# main.net
KiCad netlist of a schematic drawn in EAGLE
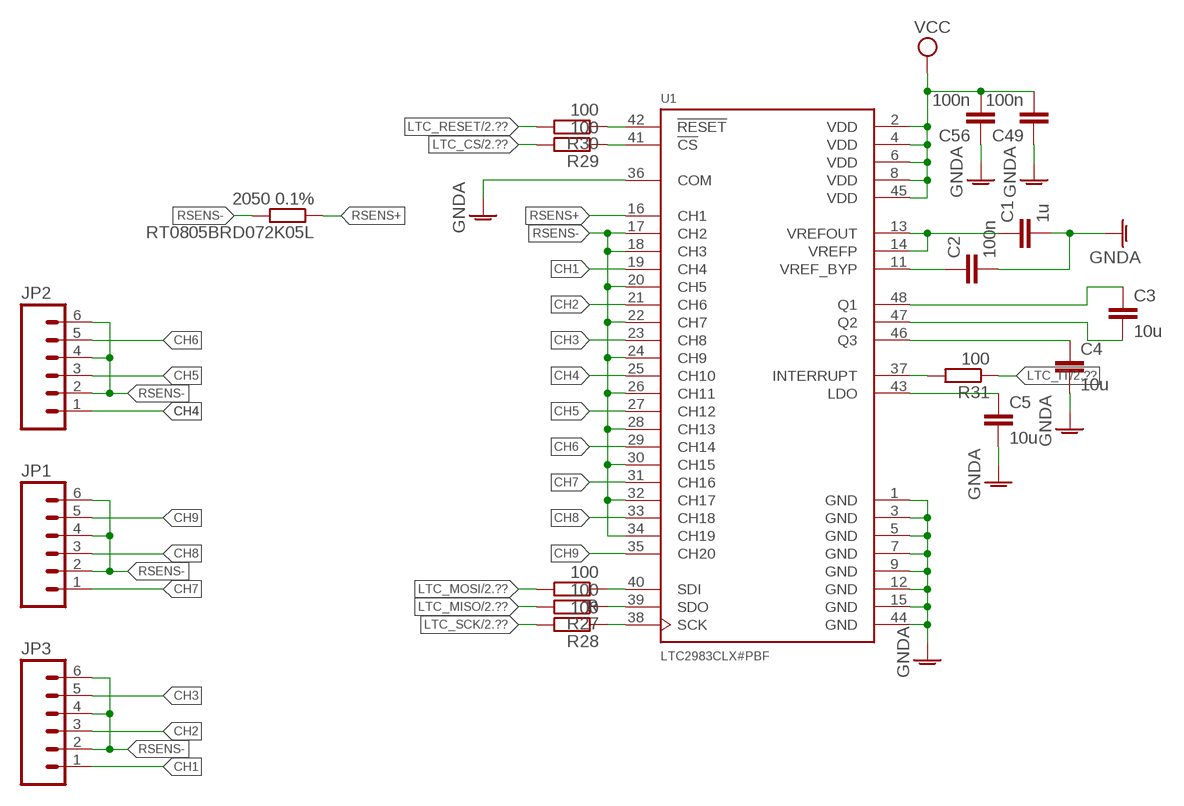
[diagram p0: schematic, sheet 1]
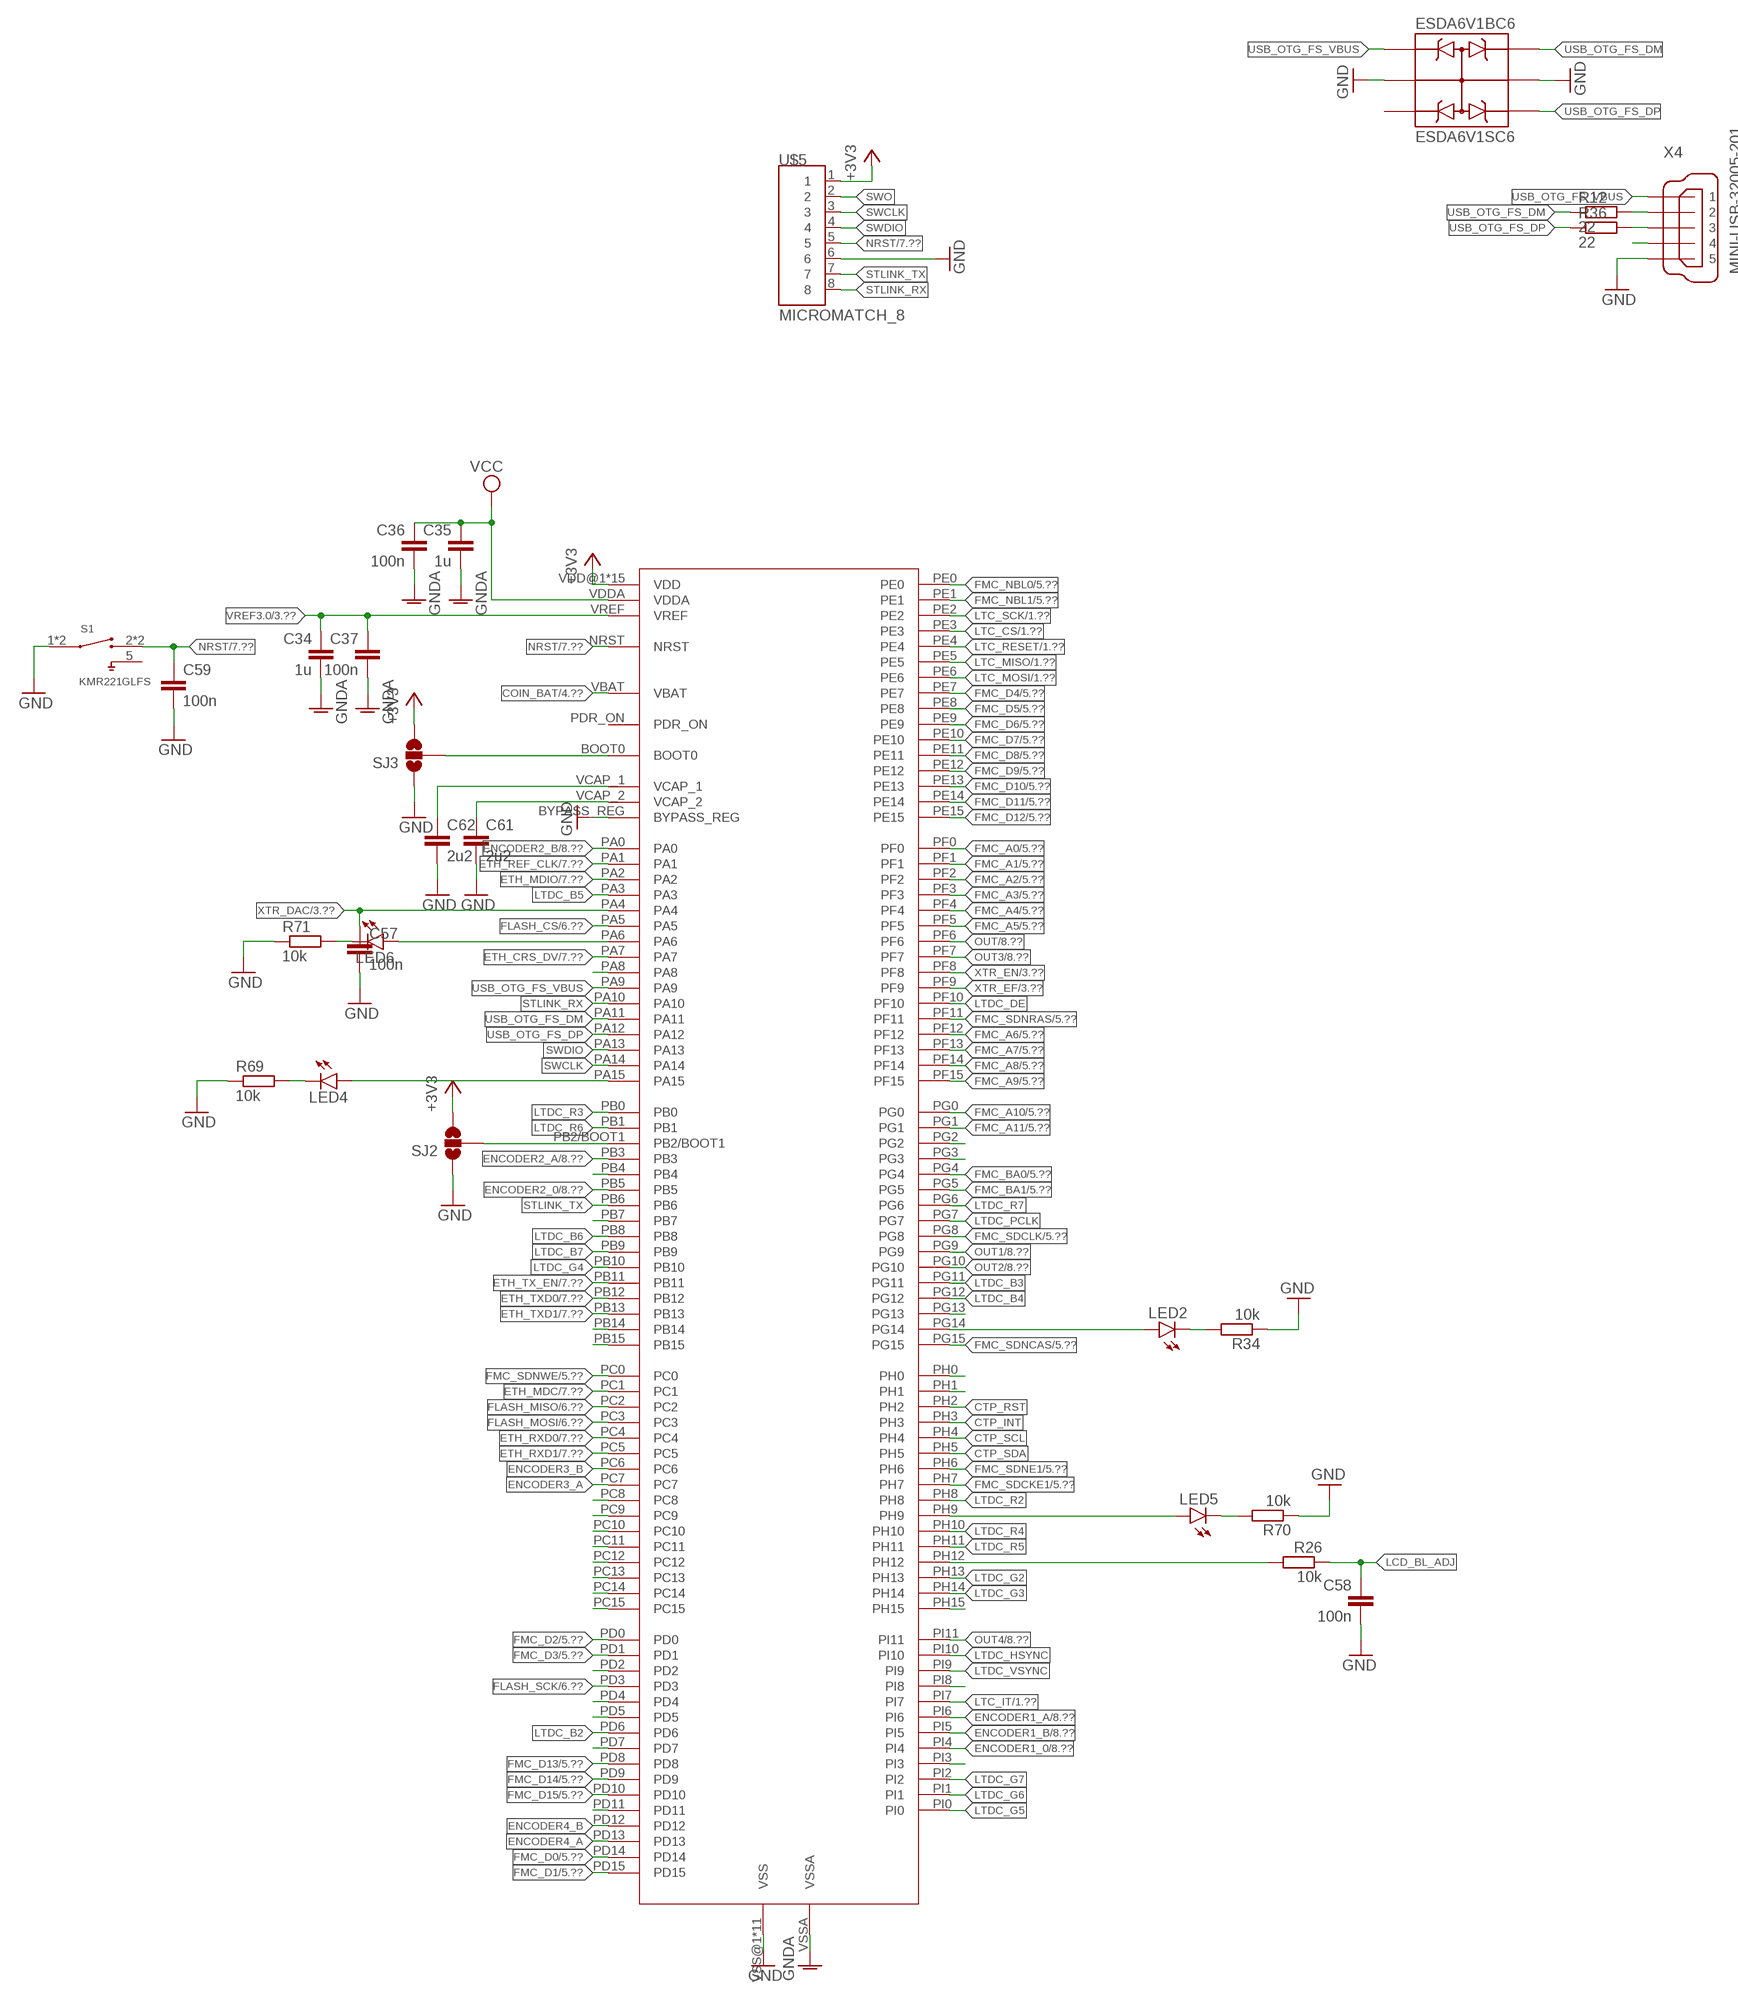
[diagram p1: schematic, sheet 2, part 1 of 2]
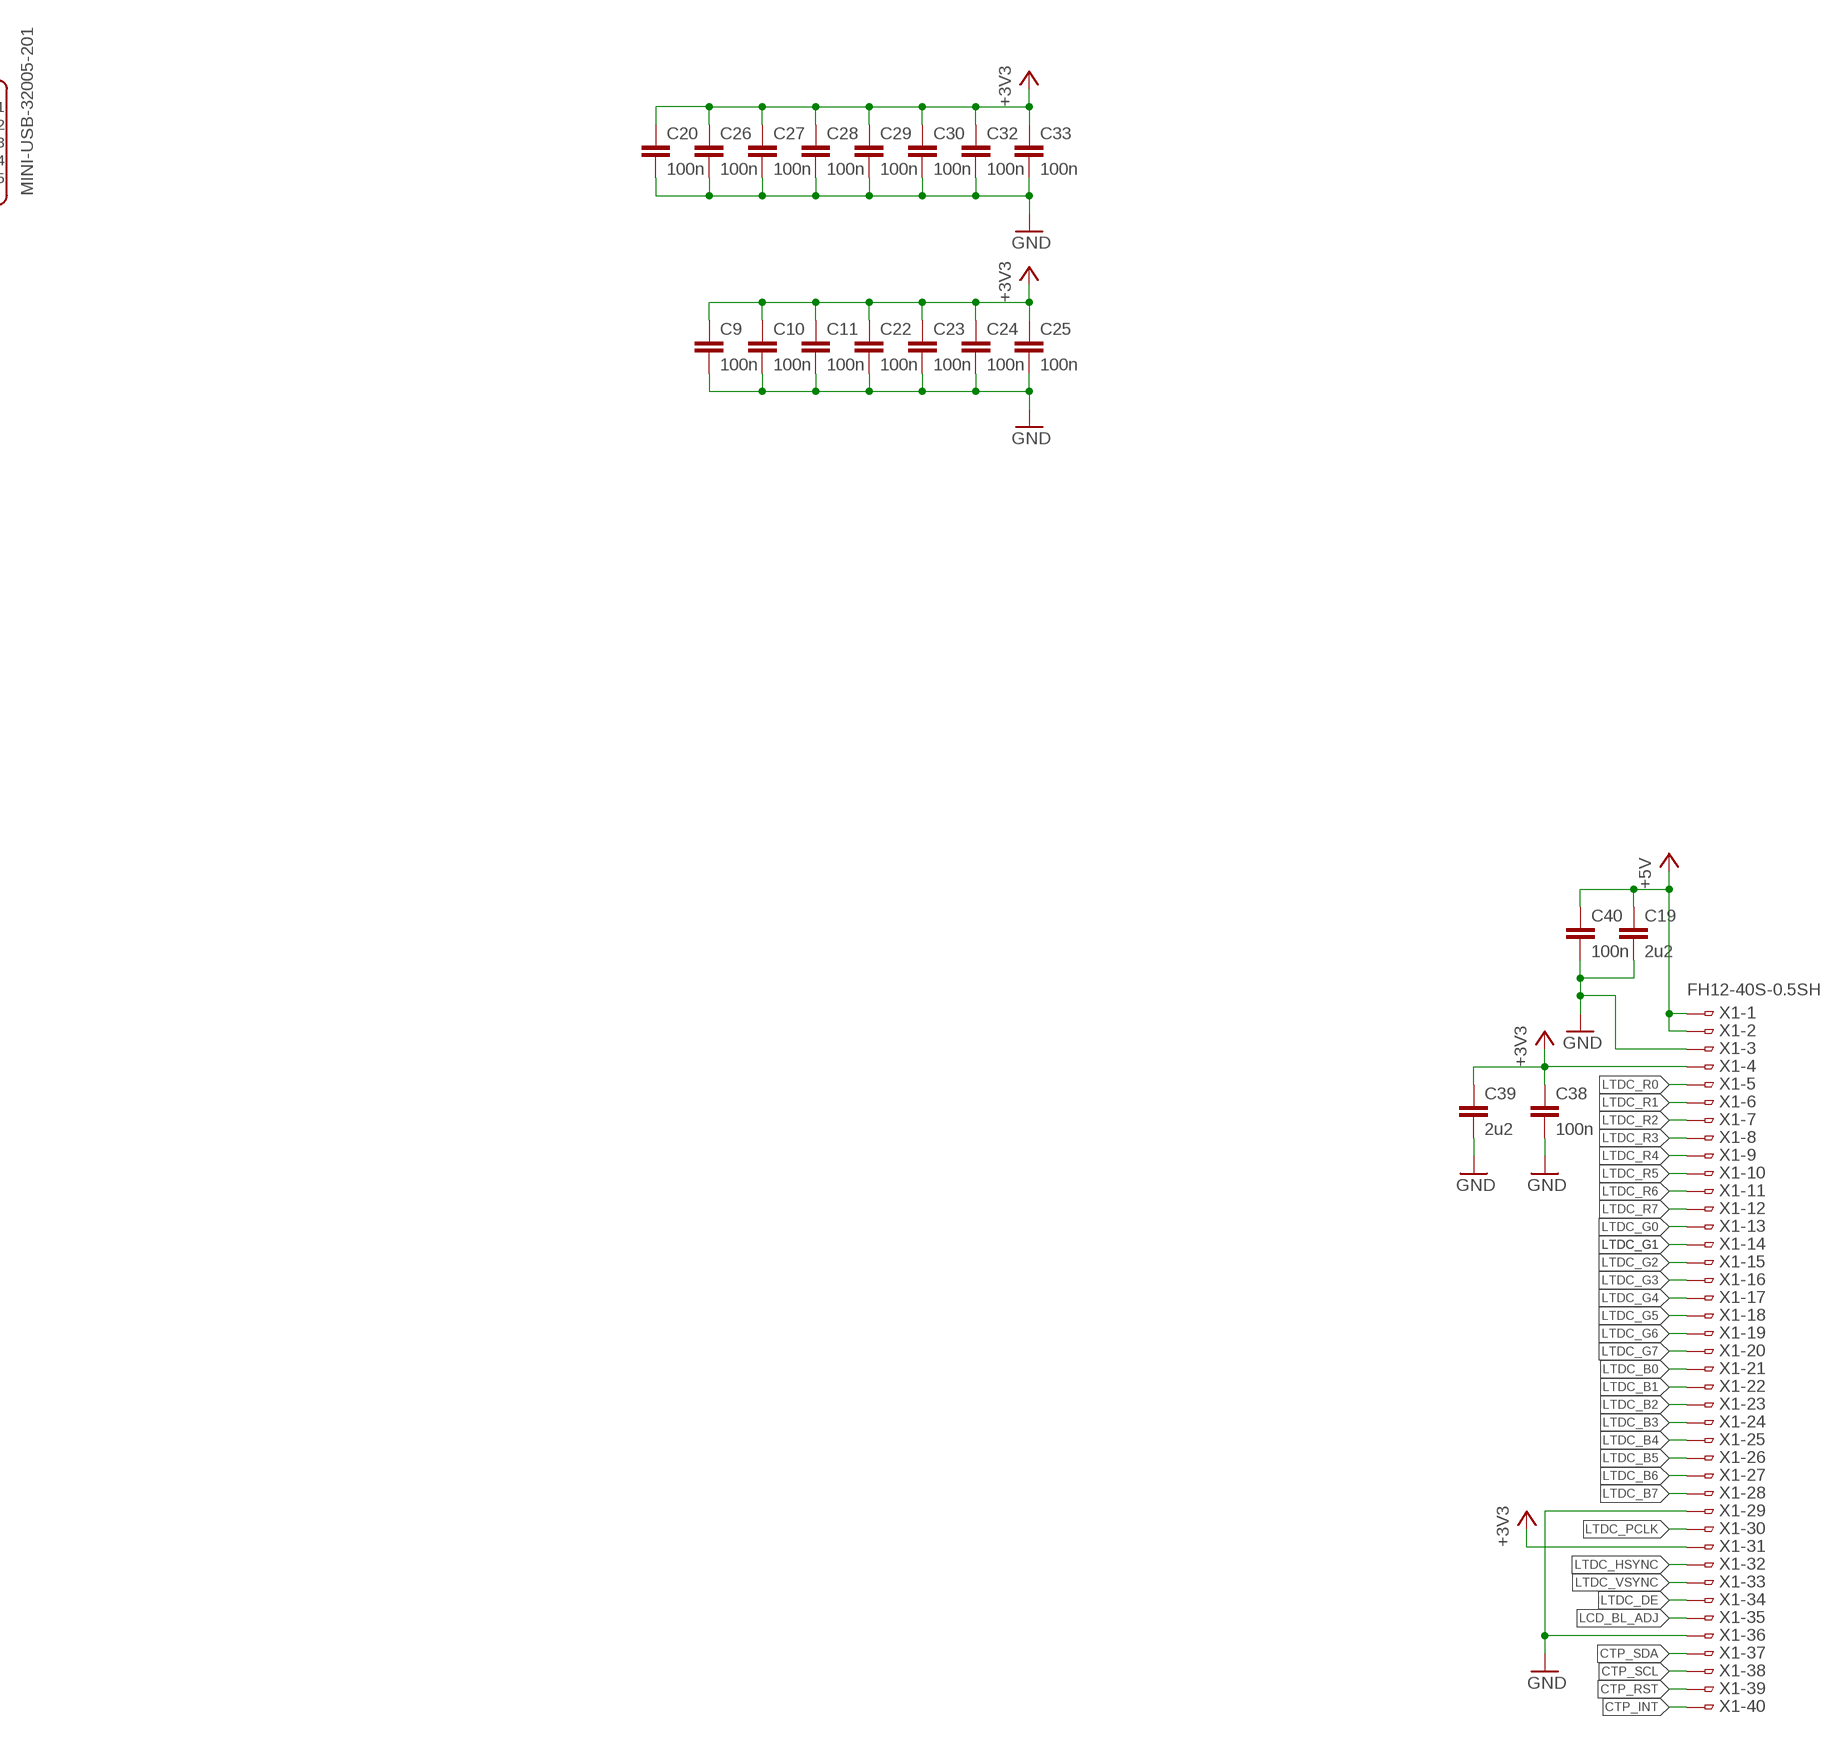
[diagram p2: schematic, sheet 2, part 2 of 2]
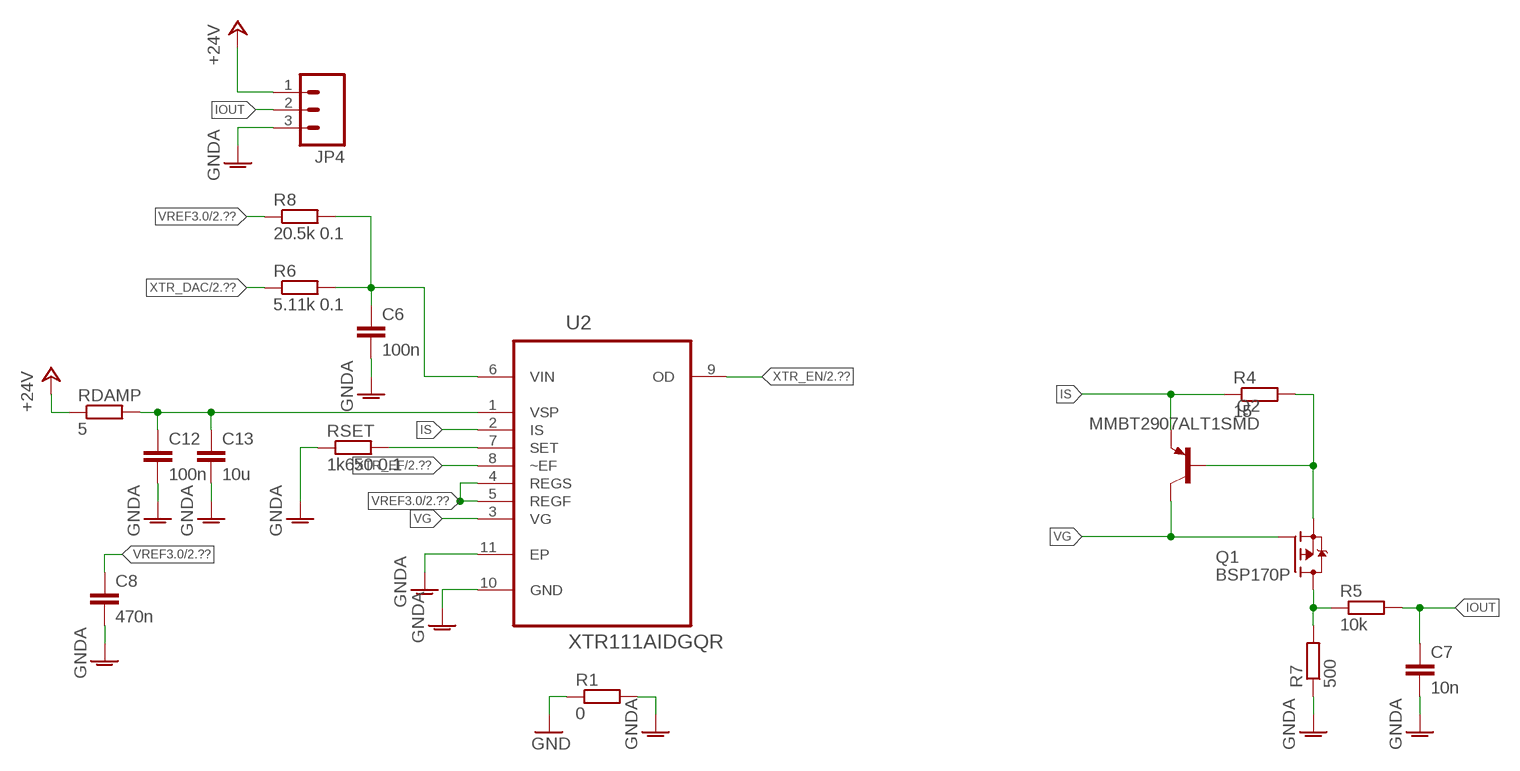
[diagram p3: schematic, sheet 3]
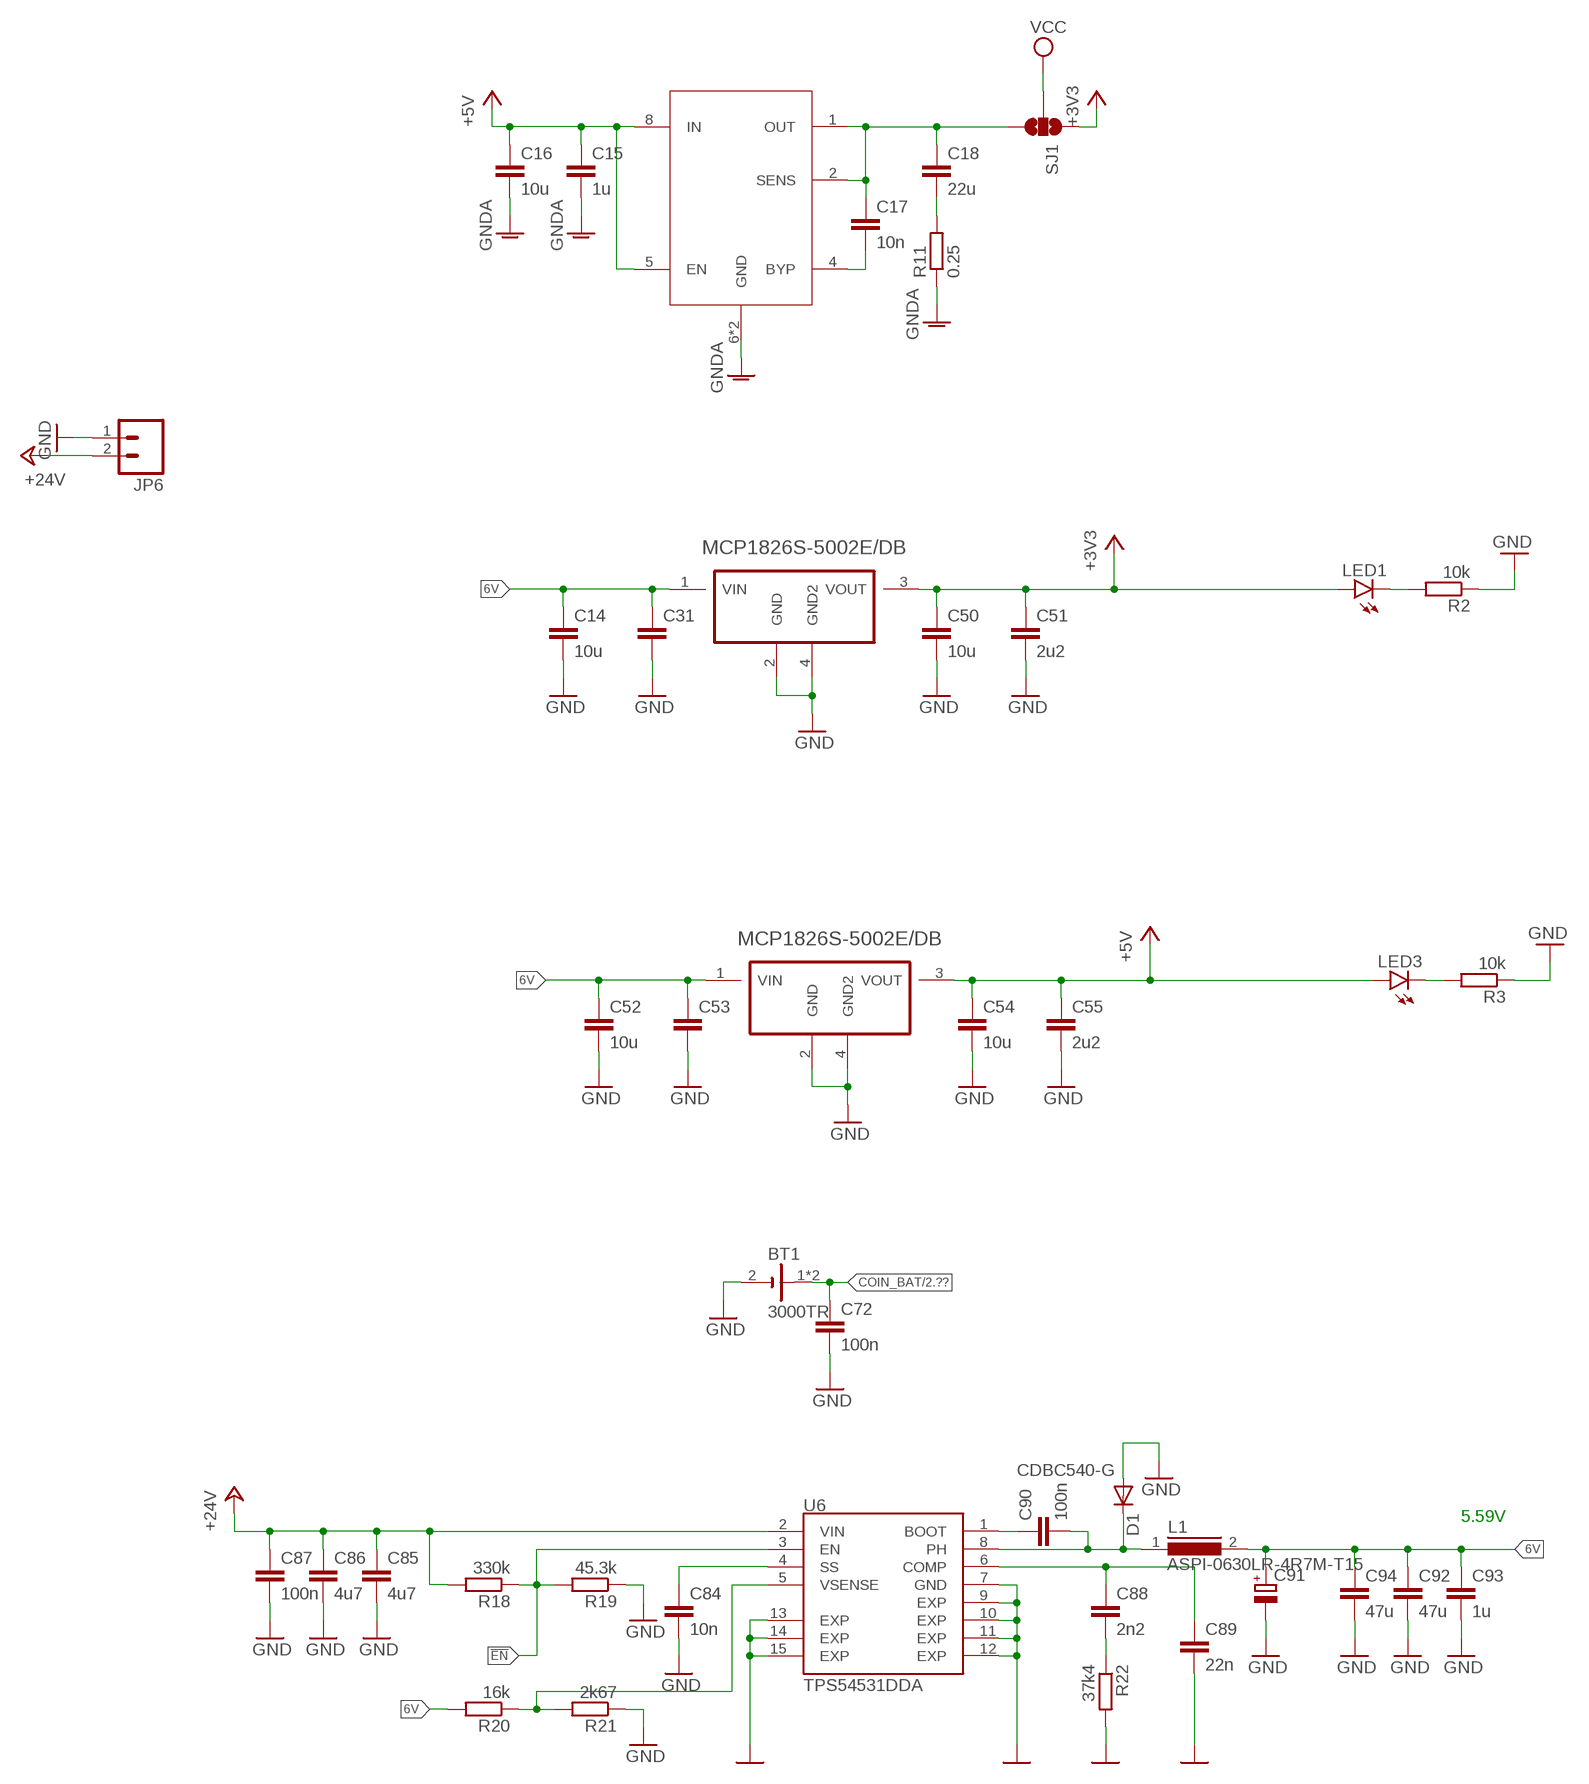
[diagram p4: schematic, sheet 4]
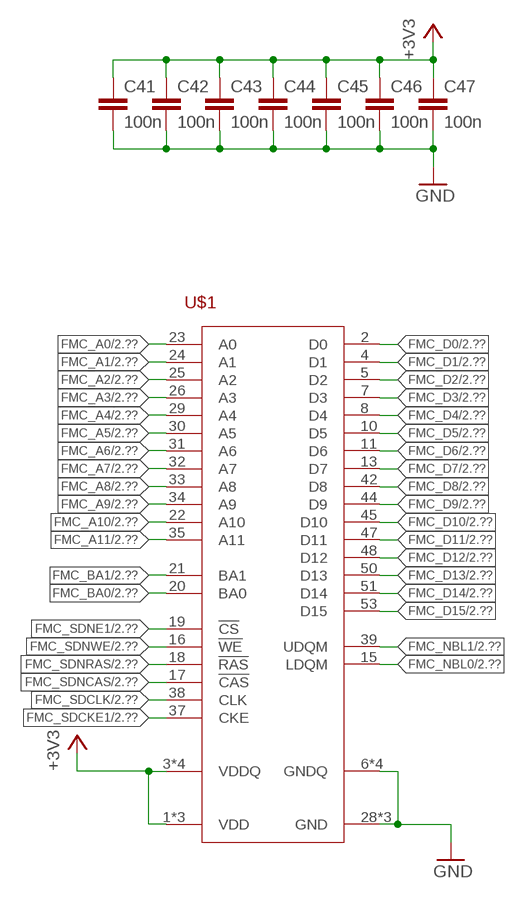
[diagram p5: schematic, sheet 5]
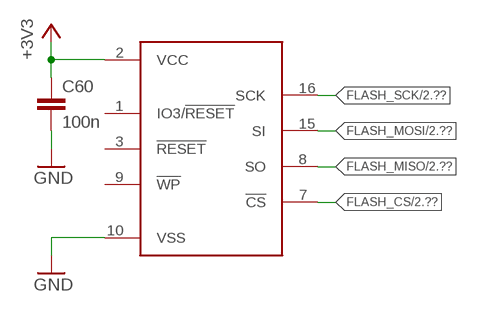
[diagram p6: schematic, sheet 6]
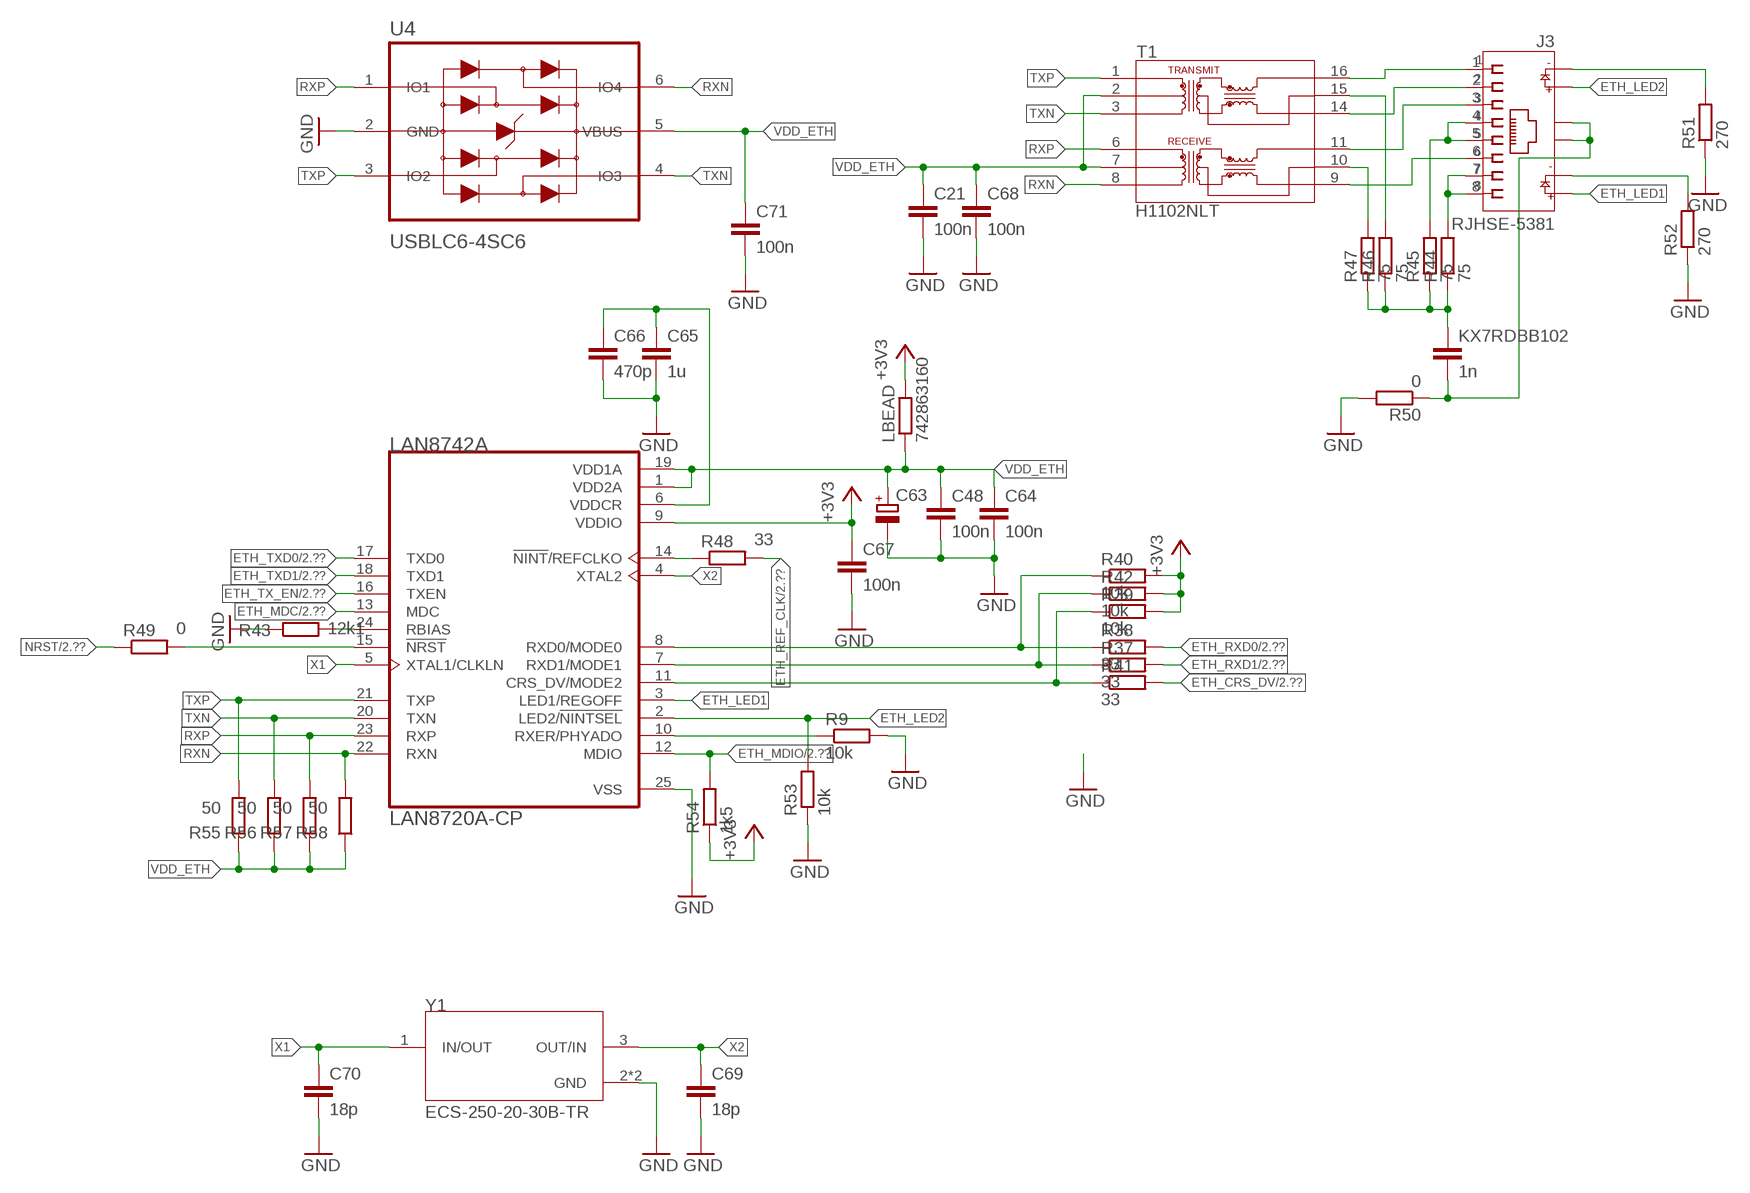
[diagram p7: schematic, sheet 7]
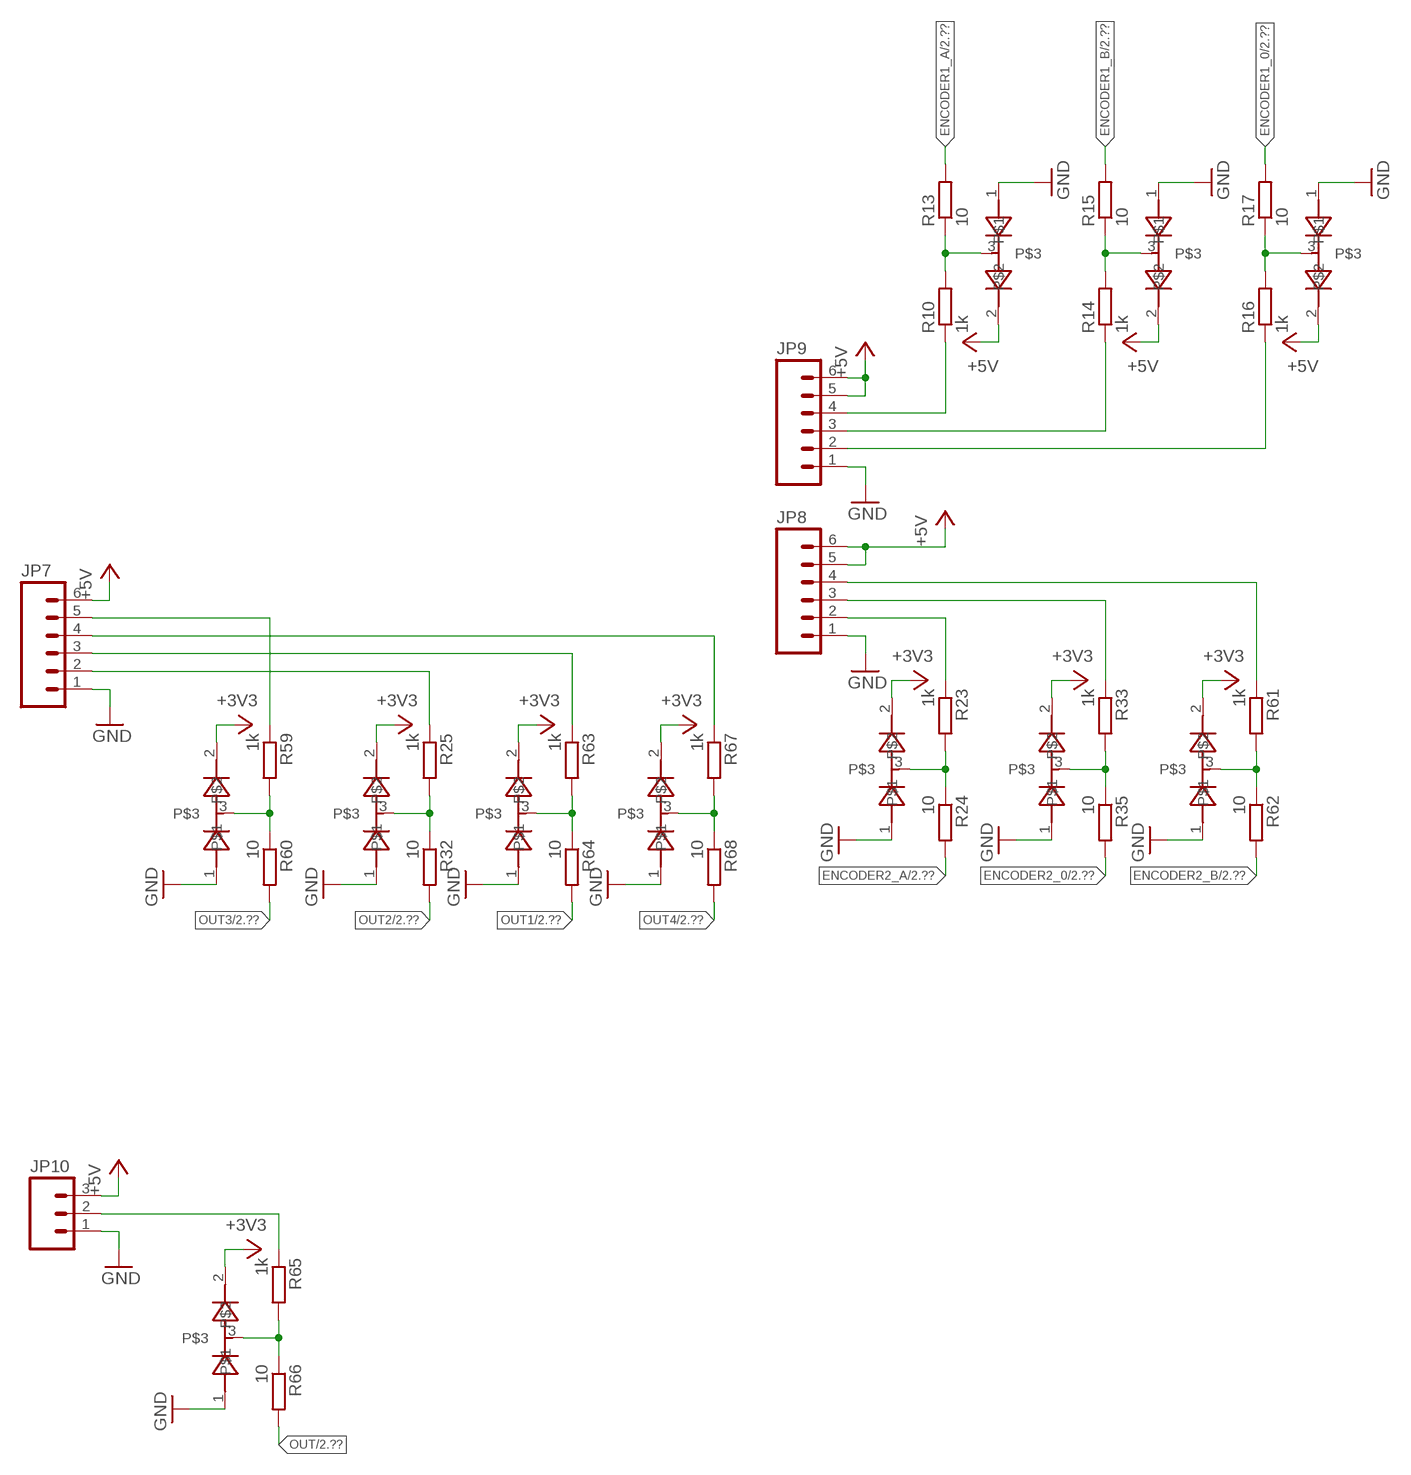
[diagram p8: schematic, sheet 8]

(export (version "E")
  (design (tool "Eeschema 10.0.6"))
  (components
    (comp (ref "C21")
      (value "100n")
      (footprint "eagle-import:C0603K")
      (libsource (lib "eagle-import") (part "rcl_334_C-EUC0603K"))
    )
    (comp (ref "C48")
      (value "100n")
      (footprint "eagle-import:C0603K")
      (libsource (lib "eagle-import") (part "rcl_334_C-EUC0603K"))
    )
    (comp (ref "C63")
      (value "CPOL-EUSMCA")
      (footprint "eagle-import:SMC_A")
      (libsource (lib "eagle-import") (part "CPOL-EUSMCA"))
    )
    (comp (ref "C64")
      (value "100n")
      (footprint "eagle-import:C0603K")
      (libsource (lib "eagle-import") (part "rcl_334_C-EUC0603K"))
    )
    (comp (ref "C65")
      (value "1u")
      (footprint "eagle-import:C0603K")
      (libsource (lib "eagle-import") (part "rcl_334_C-EUC0603K"))
    )
    (comp (ref "C66")
      (value "470p")
      (footprint "eagle-import:C0603K")
      (libsource (lib "eagle-import") (part "rcl_334_C-EUC0603K"))
    )
    (comp (ref "C67")
      (value "100n")
      (footprint "eagle-import:C0603K")
      (libsource (lib "eagle-import") (part "rcl_334_C-EUC0603K"))
    )
    (comp (ref "C68")
      (value "100n")
      (footprint "eagle-import:C0603K")
      (libsource (lib "eagle-import") (part "rcl_334_C-EUC0603K"))
    )
    (comp (ref "C69")
      (value "18p")
      (footprint "eagle-import:C0603K")
      (libsource (lib "eagle-import") (part "rcl_334_C-EUC0603K"))
    )
    (comp (ref "C70")
      (value "18p")
      (footprint "eagle-import:C0603K")
      (libsource (lib "eagle-import") (part "rcl_334_C-EUC0603K"))
    )
    (comp (ref "C71")
      (value "100n")
      (footprint "eagle-import:C0603K")
      (libsource (lib "eagle-import") (part "rcl_334_C-EUC0603K"))
    )
    (comp (ref "J3")
      (value "RJHSE-5381")
      (footprint "eagle-import:AMPHENOL_RJHSE-5381")
      (fields (field (name "MF") "Amphenol ICC"))
      (libsource (lib "eagle-import") (part "RJHSE-5381"))
    )
    (comp (ref "KX7RDBB102")
      (value "1n")
      (footprint "eagle-import:C1206K")
      (libsource (lib "eagle-import") (part "rcl_334_C-EUC1206K"))
    )
    (comp (ref "LAN8742A")
      (value "LAN8720A-CP")
      (footprint "eagle-import:QFN50P400X400X100-25N")
      (fields (field (name "MF") "SMSC"))
      (libsource (lib "eagle-import") (part "LAN8720A-CP"))
    )
    (comp (ref "LBEAD")
      (value "742863160")
      (footprint "eagle-import:R0603")
      (libsource (lib "eagle-import") (part "R-EU_R0603"))
    )
    (comp (ref "R9")
      (value "10k")
      (footprint "eagle-import:R0603")
      (libsource (lib "eagle-import") (part "R-EU_R0603"))
    )
    (comp (ref "R37")
      (value "33")
      (footprint "eagle-import:R0603")
      (libsource (lib "eagle-import") (part "R-EU_R0603"))
    )
    (comp (ref "R38")
      (value "33")
      (footprint "eagle-import:R0603")
      (libsource (lib "eagle-import") (part "R-EU_R0603"))
    )
    (comp (ref "R39")
      (value "10k")
      (footprint "eagle-import:R0603")
      (libsource (lib "eagle-import") (part "R-EU_R0603"))
    )
    (comp (ref "R40")
      (value "10k")
      (footprint "eagle-import:R0603")
      (libsource (lib "eagle-import") (part "R-EU_R0603"))
    )
    (comp (ref "R41")
      (value "33")
      (footprint "eagle-import:R0603")
      (libsource (lib "eagle-import") (part "R-EU_R0603"))
    )
    (comp (ref "R42")
      (value "10k")
      (footprint "eagle-import:R0603")
      (libsource (lib "eagle-import") (part "R-EU_R0603"))
    )
    (comp (ref "R43")
      (value "12k1")
      (footprint "eagle-import:R0603")
      (libsource (lib "eagle-import") (part "R-EU_R0603"))
    )
    (comp (ref "R44")
      (value "75")
      (footprint "eagle-import:R0603")
      (libsource (lib "eagle-import") (part "R-EU_R0603"))
    )
    (comp (ref "R45")
      (value "75")
      (footprint "eagle-import:R0603")
      (libsource (lib "eagle-import") (part "R-EU_R0603"))
    )
    (comp (ref "R46")
      (value "75")
      (footprint "eagle-import:R0603")
      (libsource (lib "eagle-import") (part "R-EU_R0603"))
    )
    (comp (ref "R47")
      (value "75")
      (footprint "eagle-import:R0603")
      (libsource (lib "eagle-import") (part "R-EU_R0603"))
    )
    (comp (ref "R48")
      (value "33")
      (footprint "eagle-import:R0603")
      (libsource (lib "eagle-import") (part "R-EU_R0603"))
    )
    (comp (ref "R49")
      (value "0")
      (footprint "eagle-import:R0603")
      (libsource (lib "eagle-import") (part "R-EU_R0603"))
    )
    (comp (ref "R50")
      (value "0")
      (footprint "eagle-import:R0603")
      (libsource (lib "eagle-import") (part "R-EU_R0603"))
    )
    (comp (ref "R51")
      (value "270")
      (footprint "eagle-import:R0603")
      (libsource (lib "eagle-import") (part "R-EU_R0603"))
    )
    (comp (ref "R52")
      (value "270")
      (footprint "eagle-import:R0603")
      (libsource (lib "eagle-import") (part "R-EU_R0603"))
    )
    (comp (ref "R53")
      (value "10k")
      (footprint "eagle-import:R0603")
      (libsource (lib "eagle-import") (part "R-EU_R0603"))
    )
    (comp (ref "R54")
      (value "1k5")
      (footprint "eagle-import:R0603")
      (libsource (lib "eagle-import") (part "R-EU_R0603"))
    )
    (comp (ref "R55")
      (value "50")
      (footprint "eagle-import:R0603")
      (libsource (lib "eagle-import") (part "R-EU_R0603"))
    )
    (comp (ref "R56")
      (value "50")
      (footprint "eagle-import:R0603")
      (libsource (lib "eagle-import") (part "R-EU_R0603"))
    )
    (comp (ref "R57")
      (value "50")
      (footprint "eagle-import:R0603")
      (libsource (lib "eagle-import") (part "R-EU_R0603"))
    )
    (comp (ref "R58")
      (value "50")
      (footprint "eagle-import:R0603")
      (libsource (lib "eagle-import") (part "R-EU_R0603"))
    )
    (comp (ref "T1")
      (value "H1102NLT")
      (footprint "eagle-import:XFMR_H1102NLT")
      (fields (field (name "MF") "Pulse Electronics"))
      (libsource (lib "eagle-import") (part "H1102NLT"))
    )
    (comp (ref "U4")
      (value "USBLC6-4SC6")
      (footprint "eagle-import:SOT95P280X145-6N")
      (fields (field (name "MF") "STMicroelectronics"))
      (libsource (lib "eagle-import") (part "USBLC6-4SC6"))
    )
    (comp (ref "Y1")
      (value "ECS-250-20-30B-TR")
      (footprint "eagle-import:XTAL_ECS-250-20-30B-TR")
      (fields (field (name "MF") "ECS Inc."))
      (libsource (lib "eagle-import") (part "ECS-250-20-30B-TR"))
    )
    (comp (ref "C6")
      (value "100n")
      (footprint "eagle-import:C0603K")
      (libsource (lib "eagle-import") (part "rcl_334_C-EUC0603K"))
    )
    (comp (ref "C7")
      (value "10n")
      (footprint "eagle-import:C0603K")
      (libsource (lib "eagle-import") (part "rcl_334_C-EUC0603K"))
    )
    (comp (ref "C8")
      (value "470n")
      (footprint "eagle-import:C0603K")
      (libsource (lib "eagle-import") (part "rcl_334_C-EUC0603K"))
    )
    (comp (ref "C12")
      (value "100n")
      (footprint "eagle-import:C0603K")
      (libsource (lib "eagle-import") (part "rcl_334_C-EUC0603K"))
    )
    (comp (ref "C13")
      (value "10u")
      (footprint "eagle-import:C0805")
      (libsource (lib "eagle-import") (part "rcl_334_C-EUC0805"))
    )
    (comp (ref "JP4")
      (value "M03SCREW")
      (footprint "eagle-import:SCREWTERMINAL-3.5MM-3")
      (libsource (lib "eagle-import") (part "M03SCREW"))
    )
    (comp (ref "Q1")
      (value "BSP170P")
      (footprint "eagle-import:SOT223")
      (libsource (lib "eagle-import") (part "BSP170P"))
    )
    (comp (ref "Q2")
      (value "MMBT2907ALT1SMD")
      (footprint "eagle-import:SOT23-BEC")
      (libsource (lib "eagle-import") (part "MMBT2907SMDALT1"))
    )
    (comp (ref "R1")
      (value "0")
      (footprint "eagle-import:R0603")
      (libsource (lib "eagle-import") (part "R-EU_R0603"))
    )
    (comp (ref "R4")
      (value "15")
      (footprint "eagle-import:R0603")
      (libsource (lib "eagle-import") (part "R-EU_R0603"))
    )
    (comp (ref "R5")
      (value "10k")
      (footprint "eagle-import:R0603")
      (libsource (lib "eagle-import") (part "R-EU_R0603"))
    )
    (comp (ref "R6")
      (value "5.11k 0.1")
      (footprint "eagle-import:R0805")
      (libsource (lib "eagle-import") (part "R-EU_R0805"))
    )
    (comp (ref "R7")
      (value "500")
      (footprint "eagle-import:R0603")
      (libsource (lib "eagle-import") (part "R-EU_R0603"))
    )
    (comp (ref "R8")
      (value "20.5k 0.1")
      (footprint "eagle-import:R0805")
      (libsource (lib "eagle-import") (part "R-EU_R0805"))
    )
    (comp (ref "RDAMP")
      (value "5")
      (footprint "eagle-import:R0603")
      (libsource (lib "eagle-import") (part "R-EU_R0603"))
    )
    (comp (ref "RSET")
      (value "1k650 0.1")
      (footprint "eagle-import:R0805")
      (libsource (lib "eagle-import") (part "R-EU_R0805"))
    )
    (comp (ref "U2")
      (value "XTR111AIDGQR")
      (footprint "eagle-import:SOP50P490X120-15N")
      (fields (field (name "MF") "Texas Instruments"))
      (libsource (lib "eagle-import") (part "XTR111AIDGQR"))
    )
    (comp (ref "C41")
      (value "100n")
      (footprint "eagle-import:C0603K")
      (libsource (lib "eagle-import") (part "rcl_334_C-EUC0603K"))
    )
    (comp (ref "C42")
      (value "100n")
      (footprint "eagle-import:C0603K")
      (libsource (lib "eagle-import") (part "rcl_334_C-EUC0603K"))
    )
    (comp (ref "C43")
      (value "100n")
      (footprint "eagle-import:C0603K")
      (libsource (lib "eagle-import") (part "rcl_334_C-EUC0603K"))
    )
    (comp (ref "C44")
      (value "100n")
      (footprint "eagle-import:C0603K")
      (libsource (lib "eagle-import") (part "rcl_334_C-EUC0603K"))
    )
    (comp (ref "C45")
      (value "100n")
      (footprint "eagle-import:C0603K")
      (libsource (lib "eagle-import") (part "rcl_334_C-EUC0603K"))
    )
    (comp (ref "C46")
      (value "100n")
      (footprint "eagle-import:C0603K")
      (libsource (lib "eagle-import") (part "rcl_334_C-EUC0603K"))
    )
    (comp (ref "C47")
      (value "100n")
      (footprint "eagle-import:C0603K")
      (libsource (lib "eagle-import") (part "rcl_334_C-EUC0603K"))
    )
    (comp (ref "U$1")
      (value "IS45S16400J")
      (footprint "eagle-import:TSOP54")
      (libsource (lib "eagle-import") (part "IS45S16400J"))
    )
    (comp (ref "C1")
      (value "1u")
      (footprint "eagle-import:C0603K")
      (libsource (lib "eagle-import") (part "rcl_334_C-EUC0603K"))
    )
    (comp (ref "C2")
      (value "100n")
      (footprint "eagle-import:C0603K")
      (libsource (lib "eagle-import") (part "rcl_334_C-EUC0603K"))
    )
    (comp (ref "C3")
      (value "10u")
      (footprint "eagle-import:C0805K")
      (libsource (lib "eagle-import") (part "rcl_334_C-EUC0805K"))
    )
    (comp (ref "C4")
      (value "10u")
      (footprint "eagle-import:C0805K")
      (libsource (lib "eagle-import") (part "rcl_334_C-EUC0805K"))
    )
    (comp (ref "C5")
      (value "10u")
      (footprint "eagle-import:C0805K")
      (libsource (lib "eagle-import") (part "rcl_334_C-EUC0805K"))
    )
    (comp (ref "C49")
      (value "100n")
      (footprint "eagle-import:C0603K")
      (libsource (lib "eagle-import") (part "rcl_334_C-EUC0603K"))
    )
    (comp (ref "C56")
      (value "100n")
      (footprint "eagle-import:C0603K")
      (libsource (lib "eagle-import") (part "rcl_334_C-EUC0603K"))
    )
    (comp (ref "JP1")
      (value "M063.5MM-6")
      (footprint "eagle-import:SCREWTERMINAL-3.5MM-6")
      (libsource (lib "eagle-import") (part "M063.5MM-6"))
    )
    (comp (ref "JP2")
      (value "M063.5MM-6")
      (footprint "eagle-import:SCREWTERMINAL-3.5MM-6")
      (libsource (lib "eagle-import") (part "M063.5MM-6"))
    )
    (comp (ref "JP3")
      (value "M063.5MM-6")
      (footprint "eagle-import:SCREWTERMINAL-3.5MM-6")
      (libsource (lib "eagle-import") (part "M063.5MM-6"))
    )
    (comp (ref "R")
      (value "100")
      (footprint "eagle-import:R0603")
      (libsource (lib "eagle-import") (part "R-EU_R0603"))
    )
    (comp (ref "R27")
      (value "100")
      (footprint "eagle-import:R0603")
      (libsource (lib "eagle-import") (part "R-EU_R0603"))
    )
    (comp (ref "R28")
      (value "100")
      (footprint "eagle-import:R0603")
      (libsource (lib "eagle-import") (part "R-EU_R0603"))
    )
    (comp (ref "R29")
      (value "100")
      (footprint "eagle-import:R0603")
      (libsource (lib "eagle-import") (part "R-EU_R0603"))
    )
    (comp (ref "R30")
      (value "100")
      (footprint "eagle-import:R0603")
      (libsource (lib "eagle-import") (part "R-EU_R0603"))
    )
    (comp (ref "R31")
      (value "100")
      (footprint "eagle-import:R0603")
      (libsource (lib "eagle-import") (part "R-EU_R0603"))
    )
    (comp (ref "RT0805BRD072K05L")
      (value "2050 0.1%")
      (footprint "eagle-import:R0805")
      (libsource (lib "eagle-import") (part "R-EU_R0805"))
    )
    (comp (ref "U1")
      (value "LTC2983CLX#PBF")
      (footprint "eagle-import:QFP50P900X900X160-48N")
      (fields (field (name "MF") "Linear Technology/Analog"))
      (libsource (lib "eagle-import") (part "LTC2983CLX#PBF"))
    )
    (comp (ref "BT1")
      (value "3000TR")
      (footprint "eagle-import:BAT_3000TR")
      (fields (field (name "MF") "Keystone"))
      (libsource (lib "eagle-import") (part "3000TR"))
    )
    (comp (ref "C14")
      (value "10u")
      (footprint "eagle-import:C0805K")
      (libsource (lib "eagle-import") (part "rcl_334_C-EUC0805K"))
    )
    (comp (ref "C15")
      (value "1u")
      (footprint "eagle-import:C0805")
      (libsource (lib "eagle-import") (part "C-EUC0805"))
    )
    (comp (ref "C16")
      (value "10u")
      (footprint "eagle-import:C0805")
      (libsource (lib "eagle-import") (part "C-EUC0805"))
    )
    (comp (ref "C17")
      (value "10n")
      (footprint "eagle-import:C0603K")
      (libsource (lib "eagle-import") (part "C-EUC0603K"))
    )
    (comp (ref "C18")
      (value "22u")
      (footprint "eagle-import:C1206")
      (libsource (lib "eagle-import") (part "C-EUC1206"))
    )
    (comp (ref "C31")
      (value "C-EUC0805K")
      (footprint "eagle-import:C0805K")
      (libsource (lib "eagle-import") (part "rcl_334_C-EUC0805K"))
    )
    (comp (ref "C50")
      (value "10u")
      (footprint "eagle-import:C0805K")
      (libsource (lib "eagle-import") (part "rcl_334_C-EUC0805K"))
    )
    (comp (ref "C51")
      (value "2u2")
      (footprint "eagle-import:C0805K")
      (libsource (lib "eagle-import") (part "rcl_334_C-EUC0805K"))
    )
    (comp (ref "C52")
      (value "10u")
      (footprint "eagle-import:C0805K")
      (libsource (lib "eagle-import") (part "rcl_334_C-EUC0805K"))
    )
    (comp (ref "C53")
      (value "C-EUC0805K")
      (footprint "eagle-import:C0805K")
      (libsource (lib "eagle-import") (part "rcl_334_C-EUC0805K"))
    )
    (comp (ref "C54")
      (value "10u")
      (footprint "eagle-import:C0805K")
      (libsource (lib "eagle-import") (part "rcl_334_C-EUC0805K"))
    )
    (comp (ref "C55")
      (value "2u2")
      (footprint "eagle-import:C0805K")
      (libsource (lib "eagle-import") (part "rcl_334_C-EUC0805K"))
    )
    (comp (ref "C72")
      (value "100n")
      (footprint "eagle-import:C0603K")
      (libsource (lib "eagle-import") (part "rcl_334_C-EUC0603K"))
    )
    (comp (ref "C84")
      (value "10n")
      (footprint "eagle-import:C0603K")
      (libsource (lib "eagle-import") (part "rcl_334_C-EUC0603K"))
    )
    (comp (ref "C85")
      (value "4u7")
      (footprint "eagle-import:C0805K")
      (libsource (lib "eagle-import") (part "rcl_334_C-EUC0805K"))
    )
    (comp (ref "C86")
      (value "4u7")
      (footprint "eagle-import:C0805K")
      (libsource (lib "eagle-import") (part "rcl_334_C-EUC0805K"))
    )
    (comp (ref "C87")
      (value "100n")
      (footprint "eagle-import:C0603K")
      (libsource (lib "eagle-import") (part "rcl_334_C-EUC0603K"))
    )
    (comp (ref "C88")
      (value "2n2")
      (footprint "eagle-import:C0603K")
      (libsource (lib "eagle-import") (part "rcl_334_C-EUC0603K"))
    )
    (comp (ref "C89")
      (value "22n")
      (footprint "eagle-import:C0603K")
      (libsource (lib "eagle-import") (part "rcl_334_C-EUC0603K"))
    )
    (comp (ref "C90")
      (value "100n")
      (footprint "eagle-import:C0603K")
      (libsource (lib "eagle-import") (part "rcl_334_C-EUC0603K"))
    )
    (comp (ref "C91")
      (value "CPOL-EUE5-6")
      (footprint "eagle-import:E5-6")
      (libsource (lib "eagle-import") (part "CPOL-EUE5-6"))
    )
    (comp (ref "C92")
      (value "47u")
      (footprint "eagle-import:C1210")
      (libsource (lib "eagle-import") (part "rcl_334_C-EUC1210"))
    )
    (comp (ref "C93")
      (value "1u")
      (footprint "eagle-import:C0603K")
      (libsource (lib "eagle-import") (part "rcl_334_C-EUC0603K"))
    )
    (comp (ref "C94")
      (value "47u")
      (footprint "eagle-import:C1210")
      (libsource (lib "eagle-import") (part "rcl_334_C-EUC1210"))
    )
    (comp (ref "D1")
      (value "CDBC540-G")
      (footprint "eagle-import:SMB")
      (libsource (lib "eagle-import") (part "DIODE-SMB"))
    )
    (comp (ref "JP6")
      (value "M023.5MM-NO_SILK")
      (footprint "eagle-import:SCREWTERMINAL-3.5MM-2-NS")
      (libsource (lib "eagle-import") (part "M023.5MM-NO_SILK"))
    )
    (comp (ref "L1")
      (value "ASPI-0630LR-4R7M-T15")
      (footprint "eagle-import:DR74")
      (libsource (lib "eagle-import") (part "DR74"))
    )
    (comp (ref "LED1")
      (value "LEDCHIPLED_0603")
      (footprint "eagle-import:CHIPLED_0603")
      (libsource (lib "eagle-import") (part "LEDCHIPLED_0603"))
    )
    (comp (ref "LED3")
      (value "LEDCHIPLED_0603")
      (footprint "eagle-import:CHIPLED_0603")
      (libsource (lib "eagle-import") (part "LEDCHIPLED_0603"))
    )
    (comp (ref "R2")
      (value "10k")
      (footprint "eagle-import:R0603")
      (libsource (lib "eagle-import") (part "R-EU_R0603"))
    )
    (comp (ref "R3")
      (value "10k")
      (footprint "eagle-import:R0603")
      (libsource (lib "eagle-import") (part "R-EU_R0603"))
    )
    (comp (ref "R11")
      (value "0.25")
      (footprint "eagle-import:R0603")
      (libsource (lib "eagle-import") (part "R-EU_R0603"))
    )
    (comp (ref "R18")
      (value "330k")
      (footprint "eagle-import:R0603")
      (libsource (lib "eagle-import") (part "R-EU_R0603"))
    )
    (comp (ref "R19")
      (value "45.3k")
      (footprint "eagle-import:R0603")
      (libsource (lib "eagle-import") (part "R-EU_R0603"))
    )
    (comp (ref "R20")
      (value "16k")
      (footprint "eagle-import:R0603")
      (libsource (lib "eagle-import") (part "R-EU_R0603"))
    )
    (comp (ref "R21")
      (value "2k67")
      (footprint "eagle-import:R0603")
      (libsource (lib "eagle-import") (part "R-EU_R0603"))
    )
    (comp (ref "R22")
      (value "37k4")
      (footprint "eagle-import:R0603")
      (libsource (lib "eagle-import") (part "R-EU_R0603"))
    )
    (comp (ref "SJ1")
      (value "SOLDERJUMPER_2WAYS")
      (footprint "eagle-import:SJ_3")
      (libsource (lib "eagle-import") (part "SOLDERJUMPER_2WAYS"))
    )
    (comp (ref "U$2")
      (value "IFX5444")
      (footprint "eagle-import:SOIC8")
      (libsource (lib "eagle-import") (part "IFX5444"))
    )
    (comp (ref "U3")
      (value "MCP1826S-5002E/DB")
      (footprint "eagle-import:SOT230P700X180-4N")
      (fields (field (name "MF") "Microchip"))
      (libsource (lib "eagle-import") (part "MCP1826S-5002E/DB"))
    )
    (comp (ref "U5")
      (value "MCP1826S-5002E/DB")
      (footprint "eagle-import:SOT230P700X180-4N")
      (fields (field (name "MF") "Microchip"))
      (libsource (lib "eagle-import") (part "MCP1826S-5002E/DB"))
    )
    (comp (ref "U6")
      (value "TPS54531DDA")
      (footprint "eagle-import:SOIC127P600X170-9N")
      (fields (field (name "MF") "Texas Instruments"))
      (libsource (lib "eagle-import") (part "TPS54531DDA"))
    )
    (comp (ref "C9")
      (value "100n")
      (footprint "eagle-import:C0603K")
      (libsource (lib "eagle-import") (part "rcl_334_C-EUC0603K"))
    )
    (comp (ref "C10")
      (value "100n")
      (footprint "eagle-import:C0603K")
      (libsource (lib "eagle-import") (part "rcl_334_C-EUC0603K"))
    )
    (comp (ref "C11")
      (value "100n")
      (footprint "eagle-import:C0603K")
      (libsource (lib "eagle-import") (part "rcl_334_C-EUC0603K"))
    )
    (comp (ref "C19")
      (value "2u2")
      (footprint "eagle-import:C0805K")
      (libsource (lib "eagle-import") (part "rcl_334_C-EUC0805K"))
    )
    (comp (ref "C20")
      (value "100n")
      (footprint "eagle-import:C0603K")
      (libsource (lib "eagle-import") (part "rcl_334_C-EUC0603K"))
    )
    (comp (ref "C22")
      (value "100n")
      (footprint "eagle-import:C0603K")
      (libsource (lib "eagle-import") (part "rcl_334_C-EUC0603K"))
    )
    (comp (ref "C23")
      (value "100n")
      (footprint "eagle-import:C0603K")
      (libsource (lib "eagle-import") (part "rcl_334_C-EUC0603K"))
    )
    (comp (ref "C24")
      (value "100n")
      (footprint "eagle-import:C0603K")
      (libsource (lib "eagle-import") (part "rcl_334_C-EUC0603K"))
    )
    (comp (ref "C25")
      (value "100n")
      (footprint "eagle-import:C0603K")
      (libsource (lib "eagle-import") (part "rcl_334_C-EUC0603K"))
    )
    (comp (ref "C26")
      (value "100n")
      (footprint "eagle-import:C0603K")
      (libsource (lib "eagle-import") (part "rcl_334_C-EUC0603K"))
    )
    (comp (ref "C27")
      (value "100n")
      (footprint "eagle-import:C0603K")
      (libsource (lib "eagle-import") (part "rcl_334_C-EUC0603K"))
    )
    (comp (ref "C28")
      (value "100n")
      (footprint "eagle-import:C0603K")
      (libsource (lib "eagle-import") (part "rcl_334_C-EUC0603K"))
    )
    (comp (ref "C29")
      (value "100n")
      (footprint "eagle-import:C0603K")
      (libsource (lib "eagle-import") (part "rcl_334_C-EUC0603K"))
    )
    (comp (ref "C30")
      (value "100n")
      (footprint "eagle-import:C0603K")
      (libsource (lib "eagle-import") (part "rcl_334_C-EUC0603K"))
    )
    (comp (ref "C32")
      (value "100n")
      (footprint "eagle-import:C0603K")
      (libsource (lib "eagle-import") (part "rcl_334_C-EUC0603K"))
    )
    (comp (ref "C33")
      (value "100n")
      (footprint "eagle-import:C0603K")
      (libsource (lib "eagle-import") (part "rcl_334_C-EUC0603K"))
    )
    (comp (ref "C34")
      (value "1u")
      (footprint "eagle-import:C0805K")
      (libsource (lib "eagle-import") (part "rcl_334_C-EUC0805K"))
    )
    (comp (ref "C35")
      (value "1u")
      (footprint "eagle-import:C0805K")
      (libsource (lib "eagle-import") (part "rcl_334_C-EUC0805K"))
    )
    (comp (ref "C36")
      (value "100n")
      (footprint "eagle-import:C0603K")
      (libsource (lib "eagle-import") (part "rcl_334_C-EUC0603K"))
    )
    (comp (ref "C37")
      (value "100n")
      (footprint "eagle-import:C0603K")
      (libsource (lib "eagle-import") (part "rcl_334_C-EUC0603K"))
    )
    (comp (ref "C38")
      (value "100n")
      (footprint "eagle-import:C0805")
      (libsource (lib "eagle-import") (part "C-EUC0805"))
    )
    (comp (ref "C39")
      (value "2u2")
      (footprint "eagle-import:C0805K")
      (libsource (lib "eagle-import") (part "rcl_334_C-EUC0805K"))
    )
    (comp (ref "C40")
      (value "100n")
      (footprint "eagle-import:C0805")
      (libsource (lib "eagle-import") (part "C-EUC0805"))
    )
    (comp (ref "C57")
      (value "100n")
      (footprint "eagle-import:C0603K")
      (libsource (lib "eagle-import") (part "rcl_334_C-EUC0603K"))
    )
    (comp (ref "C58")
      (value "100n")
      (footprint "eagle-import:C0603K")
      (libsource (lib "eagle-import") (part "rcl_334_C-EUC0603K"))
    )
    (comp (ref "C59")
      (value "100n")
      (footprint "eagle-import:C0603K")
      (libsource (lib "eagle-import") (part "rcl_334_C-EUC0603K"))
    )
    (comp (ref "C61")
      (value "2u2")
      (footprint "eagle-import:C0805K")
      (libsource (lib "eagle-import") (part "rcl_334_C-EUC0805K"))
    )
    (comp (ref "C62")
      (value "2u2")
      (footprint "eagle-import:C0805K")
      (libsource (lib "eagle-import") (part "rcl_334_C-EUC0805K"))
    )
    (comp (ref "ESDA6V1BC6")
      (value "ESDA6V1SC6")
      (footprint "eagle-import:SOT95P280X145-6N")
      (fields (field (name "MF") "STMicroelectronics"))
      (libsource (lib "eagle-import") (part "ESDA6V1SC6"))
    )
    (comp (ref "LED2")
      (value "LEDCHIPLED_0603")
      (footprint "eagle-import:CHIPLED_0603")
      (libsource (lib "eagle-import") (part "LEDCHIPLED_0603"))
    )
    (comp (ref "LED4")
      (value "LEDCHIPLED_0603")
      (footprint "eagle-import:CHIPLED_0603")
      (libsource (lib "eagle-import") (part "LEDCHIPLED_0603"))
    )
    (comp (ref "LED5")
      (value "LEDCHIPLED_0603")
      (footprint "eagle-import:CHIPLED_0603")
      (libsource (lib "eagle-import") (part "LEDCHIPLED_0603"))
    )
    (comp (ref "LED6")
      (value "LEDCHIPLED_0603")
      (footprint "eagle-import:CHIPLED_0603")
      (libsource (lib "eagle-import") (part "LEDCHIPLED_0603"))
    )
    (comp (ref "R12")
      (value "22")
      (footprint "eagle-import:R0603")
      (libsource (lib "eagle-import") (part "R-EU_R0603"))
    )
    (comp (ref "R26")
      (value "10k")
      (footprint "eagle-import:R0603")
      (libsource (lib "eagle-import") (part "R-EU_R0603"))
    )
    (comp (ref "R34")
      (value "10k")
      (footprint "eagle-import:R0603")
      (libsource (lib "eagle-import") (part "R-EU_R0603"))
    )
    (comp (ref "R36")
      (value "22")
      (footprint "eagle-import:R0603")
      (libsource (lib "eagle-import") (part "R-EU_R0603"))
    )
    (comp (ref "R69")
      (value "10k")
      (footprint "eagle-import:R0603")
      (libsource (lib "eagle-import") (part "R-EU_R0603"))
    )
    (comp (ref "R70")
      (value "10k")
      (footprint "eagle-import:R0603")
      (libsource (lib "eagle-import") (part "R-EU_R0603"))
    )
    (comp (ref "R71")
      (value "10k")
      (footprint "eagle-import:R0603")
      (libsource (lib "eagle-import") (part "R-EU_R0603"))
    )
    (comp (ref "S1")
      (value "KMR221GLFS")
      (footprint "eagle-import:SW_KMR221GLFS")
      (fields (field (name "MF") "C&K Components"))
      (libsource (lib "eagle-import") (part "KMR221GLFS"))
    )
    (comp (ref "SJ2")
      (value "SOLDERJUMPER_2WAYS")
      (footprint "eagle-import:SJ_3")
      (libsource (lib "eagle-import") (part "SOLDERJUMPER_2WAYS"))
    )
    (comp (ref "SJ3")
      (value "SOLDERJUMPER_2WAYS")
      (footprint "eagle-import:SJ_3")
      (libsource (lib "eagle-import") (part "SOLDERJUMPER_2WAYS"))
    )
    (comp (ref "U$3")
      (value "STM32F429_176")
      (footprint "eagle-import:QFP50P2600X2600X160-176N")
      (libsource (lib "eagle-import") (part "STM32F429_176"))
    )
    (comp (ref "U$5")
      (value "MICROMATCH_8")
      (footprint "eagle-import:MICROMATCH_8")
      (libsource (lib "eagle-import") (part "MICROMATCH_8"))
    )
    (comp (ref "X1")
      (value "FH12-40S-0.5SH")
      (footprint "eagle-import:FH12-40S-0.5SH")
      (fields (field (name "MPN") "FH12-40S-0.5SH(55)"))
      (libsource (lib "eagle-import") (part "FH12-40S-0.5SH"))
    )
    (comp (ref "X4")
      (value "MINI-USB-32005-201")
      (footprint "eagle-import:32005-201")
      (libsource (lib "eagle-import") (part "MINI-USB-32005-201"))
    )
    (comp (ref "JP7")
      (value "M063.5MM-6")
      (footprint "eagle-import:SCREWTERMINAL-3.5MM-6")
      (libsource (lib "eagle-import") (part "M063.5MM-6"))
    )
    (comp (ref "JP8")
      (value "M063.5MM-6")
      (footprint "eagle-import:SCREWTERMINAL-3.5MM-6")
      (libsource (lib "eagle-import") (part "M063.5MM-6"))
    )
    (comp (ref "JP9")
      (value "M063.5MM-6")
      (footprint "eagle-import:SCREWTERMINAL-3.5MM-6")
      (libsource (lib "eagle-import") (part "M063.5MM-6"))
    )
    (comp (ref "JP10")
      (value "M03SCREW")
      (footprint "eagle-import:SCREWTERMINAL-3.5MM-3")
      (libsource (lib "eagle-import") (part "M03SCREW"))
    )
    (comp (ref "R10")
      (value "1k")
      (footprint "eagle-import:R0603")
      (libsource (lib "eagle-import") (part "R-EU_R0603"))
    )
    (comp (ref "R13")
      (value "10")
      (footprint "eagle-import:R0603")
      (libsource (lib "eagle-import") (part "R-EU_R0603"))
    )
    (comp (ref "R14")
      (value "1k")
      (footprint "eagle-import:R0603")
      (libsource (lib "eagle-import") (part "R-EU_R0603"))
    )
    (comp (ref "R15")
      (value "10")
      (footprint "eagle-import:R0603")
      (libsource (lib "eagle-import") (part "R-EU_R0603"))
    )
    (comp (ref "R16")
      (value "1k")
      (footprint "eagle-import:R0603")
      (libsource (lib "eagle-import") (part "R-EU_R0603"))
    )
    (comp (ref "R17")
      (value "10")
      (footprint "eagle-import:R0603")
      (libsource (lib "eagle-import") (part "R-EU_R0603"))
    )
    (comp (ref "R23")
      (value "1k")
      (footprint "eagle-import:R0603")
      (libsource (lib "eagle-import") (part "R-EU_R0603"))
    )
    (comp (ref "R24")
      (value "10")
      (footprint "eagle-import:R0603")
      (libsource (lib "eagle-import") (part "R-EU_R0603"))
    )
    (comp (ref "R25")
      (value "1k")
      (footprint "eagle-import:R0603")
      (libsource (lib "eagle-import") (part "R-EU_R0603"))
    )
    (comp (ref "R32")
      (value "10")
      (footprint "eagle-import:R0603")
      (libsource (lib "eagle-import") (part "R-EU_R0603"))
    )
    (comp (ref "R33")
      (value "1k")
      (footprint "eagle-import:R0603")
      (libsource (lib "eagle-import") (part "R-EU_R0603"))
    )
    (comp (ref "R35")
      (value "10")
      (footprint "eagle-import:R0603")
      (libsource (lib "eagle-import") (part "R-EU_R0603"))
    )
    (comp (ref "R59")
      (value "1k")
      (footprint "eagle-import:R0603")
      (libsource (lib "eagle-import") (part "R-EU_R0603"))
    )
    (comp (ref "R60")
      (value "10")
      (footprint "eagle-import:R0603")
      (libsource (lib "eagle-import") (part "R-EU_R0603"))
    )
    (comp (ref "R61")
      (value "1k")
      (footprint "eagle-import:R0603")
      (libsource (lib "eagle-import") (part "R-EU_R0603"))
    )
    (comp (ref "R62")
      (value "10")
      (footprint "eagle-import:R0603")
      (libsource (lib "eagle-import") (part "R-EU_R0603"))
    )
    (comp (ref "R63")
      (value "1k")
      (footprint "eagle-import:R0603")
      (libsource (lib "eagle-import") (part "R-EU_R0603"))
    )
    (comp (ref "R64")
      (value "10")
      (footprint "eagle-import:R0603")
      (libsource (lib "eagle-import") (part "R-EU_R0603"))
    )
    (comp (ref "R65")
      (value "1k")
      (footprint "eagle-import:R0603")
      (libsource (lib "eagle-import") (part "R-EU_R0603"))
    )
    (comp (ref "R66")
      (value "10")
      (footprint "eagle-import:R0603")
      (libsource (lib "eagle-import") (part "R-EU_R0603"))
    )
    (comp (ref "R67")
      (value "1k")
      (footprint "eagle-import:R0603")
      (libsource (lib "eagle-import") (part "R-EU_R0603"))
    )
    (comp (ref "R68")
      (value "10")
      (footprint "eagle-import:R0603")
      (libsource (lib "eagle-import") (part "R-EU_R0603"))
    )
    (comp (ref "U$6")
      (value "BAS40W-04")
      (footprint "eagle-import:SOT65P210X110-3N")
      (libsource (lib "eagle-import") (part "BAS40W-04"))
    )
    (comp (ref "U$8")
      (value "BAS40W-04")
      (footprint "eagle-import:SOT65P210X110-3N")
      (libsource (lib "eagle-import") (part "BAS40W-04"))
    )
    (comp (ref "U$9")
      (value "BAS40W-04")
      (footprint "eagle-import:SOT65P210X110-3N")
      (libsource (lib "eagle-import") (part "BAS40W-04"))
    )
    (comp (ref "U$10")
      (value "BAS40W-04")
      (footprint "eagle-import:SOT65P210X110-3N")
      (libsource (lib "eagle-import") (part "BAS40W-04"))
    )
    (comp (ref "U$11")
      (value "BAS40W-04")
      (footprint "eagle-import:SOT65P210X110-3N")
      (libsource (lib "eagle-import") (part "BAS40W-04"))
    )
    (comp (ref "U$12")
      (value "BAS40W-04")
      (footprint "eagle-import:SOT65P210X110-3N")
      (libsource (lib "eagle-import") (part "BAS40W-04"))
    )
    (comp (ref "U$13")
      (value "BAS40W-04")
      (footprint "eagle-import:SOT65P210X110-3N")
      (libsource (lib "eagle-import") (part "BAS40W-04"))
    )
    (comp (ref "U$14")
      (value "BAS40W-04")
      (footprint "eagle-import:SOT65P210X110-3N")
      (libsource (lib "eagle-import") (part "BAS40W-04"))
    )
    (comp (ref "U$15")
      (value "BAS40W-04")
      (footprint "eagle-import:SOT65P210X110-3N")
      (libsource (lib "eagle-import") (part "BAS40W-04"))
    )
    (comp (ref "U$16")
      (value "BAS40W-04")
      (footprint "eagle-import:SOT65P210X110-3N")
      (libsource (lib "eagle-import") (part "BAS40W-04"))
    )
    (comp (ref "U$17")
      (value "BAS40W-04")
      (footprint "eagle-import:SOT65P210X110-3N")
      (libsource (lib "eagle-import") (part "BAS40W-04"))
    )
    (comp (ref "C60")
      (value "100n")
      (footprint "eagle-import:C0603K")
      (libsource (lib "eagle-import") (part "rcl_334_C-EUC0603K"))
    )
    (comp (ref "U$4")
      (value "S25FLX")
      (footprint "eagle-import:SOIC16")
      (libsource (lib "eagle-import") (part "S25FLX"))
    )
  )
  (nets
    (net (code "1") (name "+3V3") (class "Default")
      (node (ref "C10") (pin "1") (pinfunction "1_1") (pintype "passive"))
      (node (ref "C11") (pin "1") (pinfunction "1_1") (pintype "passive"))
      (node (ref "C20") (pin "1") (pinfunction "1_1") (pintype "passive"))
      (node (ref "C22") (pin "1") (pinfunction "1_1") (pintype "passive"))
      (node (ref "C23") (pin "1") (pinfunction "1_1") (pintype "passive"))
      (node (ref "C24") (pin "1") (pinfunction "1_1") (pintype "passive"))
      (node (ref "C25") (pin "1") (pinfunction "1_1") (pintype "passive"))
      (node (ref "C26") (pin "1") (pinfunction "1_1") (pintype "passive"))
      (node (ref "C27") (pin "1") (pinfunction "1_1") (pintype "passive"))
      (node (ref "C28") (pin "1") (pinfunction "1_1") (pintype "passive"))
      (node (ref "C29") (pin "1") (pinfunction "1_1") (pintype "passive"))
      (node (ref "C30") (pin "1") (pinfunction "1_1") (pintype "passive"))
      (node (ref "C32") (pin "1") (pinfunction "1_1") (pintype "passive"))
      (node (ref "C33") (pin "1") (pinfunction "1_1") (pintype "passive"))
      (node (ref "C38") (pin "1") (pinfunction "1_1") (pintype "passive"))
      (node (ref "C39") (pin "1") (pinfunction "1_1") (pintype "passive"))
      (node (ref "C41") (pin "1") (pinfunction "1_1") (pintype "passive"))
      (node (ref "C42") (pin "1") (pinfunction "1_1") (pintype "passive"))
      (node (ref "C43") (pin "1") (pinfunction "1_1") (pintype "passive"))
      (node (ref "C44") (pin "1") (pinfunction "1_1") (pintype "passive"))
      (node (ref "C45") (pin "1") (pinfunction "1_1") (pintype "passive"))
      (node (ref "C46") (pin "1") (pinfunction "1_1") (pintype "passive"))
      (node (ref "C47") (pin "1") (pinfunction "1_1") (pintype "passive"))
      (node (ref "C50") (pin "1") (pinfunction "1_1") (pintype "passive"))
      (node (ref "C51") (pin "1") (pinfunction "1_1") (pintype "passive"))
      (node (ref "C60") (pin "1") (pinfunction "1_1") (pintype "passive"))
      (node (ref "C67") (pin "1") (pinfunction "1_1") (pintype "passive"))
      (node (ref "C9") (pin "1") (pinfunction "1_1") (pintype "passive"))
      (node (ref "LAN8742A") (pin "9") (pinfunction "VDDIO_9") (pintype "power_in"))
      (node (ref "LBEAD") (pin "2") (pinfunction "2_2") (pintype "passive"))
      (node (ref "LED1") (pin "A") (pinfunction "A_A") (pintype "passive"))
      (node (ref "R39") (pin "2") (pinfunction "2_2") (pintype "passive"))
      (node (ref "R40") (pin "2") (pinfunction "2_2") (pintype "passive"))
      (node (ref "R42") (pin "2") (pinfunction "2_2") (pintype "passive"))
      (node (ref "R54") (pin "1") (pinfunction "1_1") (pintype "passive"))
      (node (ref "SJ1") (pin "1") (pinfunction "1_1") (pintype "passive"))
      (node (ref "SJ2") (pin "3") (pinfunction "3_3") (pintype "passive"))
      (node (ref "SJ3") (pin "3") (pinfunction "3_3") (pintype "passive"))
      (node (ref "U$1") (pin "1") (pinfunction "VDD_1") (pintype "bidirectional"))
      (node (ref "U$1") (pin "14") (pinfunction "VDD_14") (pintype "bidirectional"))
      (node (ref "U$1") (pin "27") (pinfunction "VDD_27") (pintype "bidirectional"))
      (node (ref "U$1") (pin "3") (pinfunction "VDDQ_3") (pintype "bidirectional"))
      (node (ref "U$1") (pin "43") (pinfunction "VDDQ_43") (pintype "bidirectional"))
      (node (ref "U$1") (pin "49") (pinfunction "VDDQ_49") (pintype "bidirectional"))
      (node (ref "U$1") (pin "9") (pinfunction "VDDQ_9") (pintype "bidirectional"))
      (node (ref "U$10") (pin "2") (pinfunction "P$2_2") (pintype "bidirectional"))
      (node (ref "U$11") (pin "2") (pinfunction "P$2_2") (pintype "bidirectional"))
      (node (ref "U$12") (pin "2") (pinfunction "P$2_2") (pintype "bidirectional"))
      (node (ref "U$13") (pin "2") (pinfunction "P$2_2") (pintype "bidirectional"))
      (node (ref "U$14") (pin "2") (pinfunction "P$2_2") (pintype "bidirectional"))
      (node (ref "U$15") (pin "2") (pinfunction "P$2_2") (pintype "bidirectional"))
      (node (ref "U$16") (pin "2") (pinfunction "P$2_2") (pintype "bidirectional"))
      (node (ref "U$17") (pin "2") (pinfunction "P$2_2") (pintype "bidirectional"))
      (node (ref "U$3") (pin "VDD@1") (pinfunction "VDD_VDD@1") (pintype "bidirectional"))
      (node (ref "U$3") (pin "VDD@10") (pinfunction "VDD_VDD@10") (pintype "bidirectional"))
      (node (ref "U$3") (pin "VDD@11") (pinfunction "VDD_VDD@11") (pintype "bidirectional"))
      (node (ref "U$3") (pin "VDD@12") (pinfunction "VDD_VDD@12") (pintype "bidirectional"))
      (node (ref "U$3") (pin "VDD@13") (pinfunction "VDD_VDD@13") (pintype "bidirectional"))
      (node (ref "U$3") (pin "VDD@14") (pinfunction "VDD_VDD@14") (pintype "bidirectional"))
      (node (ref "U$3") (pin "VDD@15") (pinfunction "VDD_VDD@15") (pintype "bidirectional"))
      (node (ref "U$3") (pin "VDD@2") (pinfunction "VDD_VDD@2") (pintype "bidirectional"))
      (node (ref "U$3") (pin "VDD@3") (pinfunction "VDD_VDD@3") (pintype "bidirectional"))
      (node (ref "U$3") (pin "VDD@4") (pinfunction "VDD_VDD@4") (pintype "bidirectional"))
      (node (ref "U$3") (pin "VDD@5") (pinfunction "VDD_VDD@5") (pintype "bidirectional"))
      (node (ref "U$3") (pin "VDD@6") (pinfunction "VDD_VDD@6") (pintype "bidirectional"))
      (node (ref "U$3") (pin "VDD@7") (pinfunction "VDD_VDD@7") (pintype "bidirectional"))
      (node (ref "U$3") (pin "VDD@8") (pinfunction "VDD_VDD@8") (pintype "bidirectional"))
      (node (ref "U$3") (pin "VDD@9") (pinfunction "VDD_VDD@9") (pintype "bidirectional"))
      (node (ref "U$4") (pin "2") (pinfunction "VCC_2") (pintype "bidirectional"))
      (node (ref "U$5") (pin "1") (pinfunction "1_1") (pintype "passive"))
      (node (ref "U3") (pin "3") (pinfunction "VOUT_3") (pintype "output"))
      (node (ref "X1") (pin "31") (pinfunction "1_31") (pintype "passive"))
      (node (ref "X1") (pin "4") (pinfunction "1_4") (pintype "passive"))
    )
    (net (code "2") (name "+5V") (class "Default")
      (node (ref "C15") (pin "1") (pinfunction "1_1") (pintype "passive"))
      (node (ref "C16") (pin "1") (pinfunction "1_1") (pintype "passive"))
      (node (ref "C19") (pin "1") (pinfunction "1_1") (pintype "passive"))
      (node (ref "C40") (pin "1") (pinfunction "1_1") (pintype "passive"))
      (node (ref "C54") (pin "1") (pinfunction "1_1") (pintype "passive"))
      (node (ref "C55") (pin "1") (pinfunction "1_1") (pintype "passive"))
      (node (ref "JP10") (pin "3") (pinfunction "3_3") (pintype "passive"))
      (node (ref "JP7") (pin "6") (pinfunction "6_6") (pintype "passive"))
      (node (ref "JP8") (pin "5") (pinfunction "5_5") (pintype "passive"))
      (node (ref "JP8") (pin "6") (pinfunction "6_6") (pintype "passive"))
      (node (ref "JP9") (pin "5") (pinfunction "5_5") (pintype "passive"))
      (node (ref "JP9") (pin "6") (pinfunction "6_6") (pintype "passive"))
      (node (ref "LED3") (pin "A") (pinfunction "A_A") (pintype "passive"))
      (node (ref "U$2") (pin "5") (pinfunction "EN_5") (pintype "bidirectional"))
      (node (ref "U$2") (pin "8") (pinfunction "IN_8") (pintype "bidirectional"))
      (node (ref "U$6") (pin "2") (pinfunction "P$2_2") (pintype "bidirectional"))
      (node (ref "U$8") (pin "2") (pinfunction "P$2_2") (pintype "bidirectional"))
      (node (ref "U$9") (pin "2") (pinfunction "P$2_2") (pintype "bidirectional"))
      (node (ref "U5") (pin "3") (pinfunction "VOUT_3") (pintype "output"))
      (node (ref "X1") (pin "1") (pinfunction "1_1") (pintype "passive"))
      (node (ref "X1") (pin "2") (pinfunction "1_2") (pintype "passive"))
    )
    (net (code "3") (name "+24V") (class "Default")
      (node (ref "C85") (pin "1") (pinfunction "1_1") (pintype "passive"))
      (node (ref "C86") (pin "1") (pinfunction "1_1") (pintype "passive"))
      (node (ref "C87") (pin "1") (pinfunction "1_1") (pintype "passive"))
      (node (ref "JP4") (pin "1") (pinfunction "1_1") (pintype "passive"))
      (node (ref "JP6") (pin "2") (pinfunction "2_2") (pintype "passive"))
      (node (ref "R18") (pin "2") (pinfunction "2_2") (pintype "passive"))
      (node (ref "RDAMP") (pin "1") (pinfunction "1_1") (pintype "passive"))
      (node (ref "U6") (pin "2") (pinfunction "VIN_2") (pintype "input"))
    )
    (net (code "4") (name "6V") (class "Default")
      (node (ref "C14") (pin "1") (pinfunction "1_1") (pintype "passive"))
      (node (ref "C31") (pin "1") (pinfunction "1_1") (pintype "passive"))
      (node (ref "C52") (pin "1") (pinfunction "1_1") (pintype "passive"))
      (node (ref "C53") (pin "1") (pinfunction "1_1") (pintype "passive"))
      (node (ref "C91") (pin "+") (pinfunction "+_+") (pintype "passive"))
      (node (ref "C92") (pin "1") (pinfunction "1_1") (pintype "passive"))
      (node (ref "C93") (pin "1") (pinfunction "1_1") (pintype "passive"))
      (node (ref "C94") (pin "1") (pinfunction "1_1") (pintype "passive"))
      (node (ref "L1") (pin "2") (pinfunction "2_2") (pintype "passive"))
      (node (ref "R20") (pin "2") (pinfunction "2_2") (pintype "passive"))
      (node (ref "U3") (pin "1") (pinfunction "VIN_1") (pintype "input"))
      (node (ref "U5") (pin "1") (pinfunction "VIN_1") (pintype "input"))
    )
    (net (code "5") (name "CH1") (class "Default")
      (node (ref "JP3") (pin "1") (pinfunction "1_1") (pintype "passive"))
      (node (ref "U1") (pin "19") (pinfunction "CH4_19") (pintype "input"))
    )
    (net (code "6") (name "CH2") (class "Default")
      (node (ref "JP3") (pin "3") (pinfunction "3_3") (pintype "passive"))
      (node (ref "U1") (pin "21") (pinfunction "CH6_21") (pintype "input"))
    )
    (net (code "7") (name "CH3") (class "Default")
      (node (ref "JP3") (pin "5") (pinfunction "5_5") (pintype "passive"))
      (node (ref "U1") (pin "23") (pinfunction "CH8_23") (pintype "input"))
    )
    (net (code "8") (name "CH4") (class "Default")
      (node (ref "JP2") (pin "1") (pinfunction "1_1") (pintype "passive"))
      (node (ref "U1") (pin "25") (pinfunction "CH10_25") (pintype "input"))
    )
    (net (code "9") (name "CH5") (class "Default")
      (node (ref "JP2") (pin "3") (pinfunction "3_3") (pintype "passive"))
      (node (ref "U1") (pin "27") (pinfunction "CH12_27") (pintype "input"))
    )
    (net (code "10") (name "CH6") (class "Default")
      (node (ref "JP2") (pin "5") (pinfunction "5_5") (pintype "passive"))
      (node (ref "U1") (pin "29") (pinfunction "CH14_29") (pintype "input"))
    )
    (net (code "11") (name "CH7") (class "Default")
      (node (ref "JP1") (pin "1") (pinfunction "1_1") (pintype "passive"))
      (node (ref "U1") (pin "31") (pinfunction "CH16_31") (pintype "input"))
    )
    (net (code "12") (name "CH8") (class "Default")
      (node (ref "JP1") (pin "3") (pinfunction "3_3") (pintype "passive"))
      (node (ref "U1") (pin "33") (pinfunction "CH18_33") (pintype "input"))
    )
    (net (code "13") (name "CH9") (class "Default")
      (node (ref "JP1") (pin "5") (pinfunction "5_5") (pintype "passive"))
      (node (ref "U1") (pin "35") (pinfunction "CH20_35") (pintype "input"))
    )
    (net (code "14") (name "COIN_BAT") (class "Default")
      (node (ref "BT1") (pin "1") (pinfunction "+_1") (pintype "passive"))
      (node (ref "BT1") (pin "3") (pinfunction "+_3") (pintype "passive"))
      (node (ref "C72") (pin "1") (pinfunction "1_1") (pintype "passive"))
      (node (ref "U$3") (pin "VBAT") (pinfunction "VBAT_VBAT") (pintype "bidirectional"))
    )
    (net (code "15") (name "CTP_INT") (class "Default")
      (node (ref "U$3") (pin "PH3") (pinfunction "PH3_PH3") (pintype "bidirectional"))
      (node (ref "X1") (pin "40") (pinfunction "1_40") (pintype "passive"))
    )
    (net (code "16") (name "CTP_RST") (class "Default")
      (node (ref "U$3") (pin "PH2") (pinfunction "PH2_PH2") (pintype "bidirectional"))
      (node (ref "X1") (pin "39") (pinfunction "1_39") (pintype "passive"))
    )
    (net (code "17") (name "CTP_SCL") (class "Default")
      (node (ref "U$3") (pin "PH4") (pinfunction "PH4_PH4") (pintype "bidirectional"))
      (node (ref "X1") (pin "38") (pinfunction "1_38") (pintype "passive"))
    )
    (net (code "18") (name "CTP_SDA") (class "Default")
      (node (ref "U$3") (pin "PH5") (pinfunction "PH5_PH5") (pintype "bidirectional"))
      (node (ref "X1") (pin "37") (pinfunction "1_37") (pintype "passive"))
    )
    (net (code "19") (name "ENCODER1_0") (class "Default")
      (node (ref "R17") (pin "2") (pinfunction "2_2") (pintype "passive"))
      (node (ref "U$3") (pin "PI4") (pinfunction "PI4_PI4") (pintype "bidirectional"))
    )
    (net (code "20") (name "ENCODER1_A") (class "Default")
      (node (ref "R13") (pin "2") (pinfunction "2_2") (pintype "passive"))
      (node (ref "U$3") (pin "PI6") (pinfunction "PI6_PI6") (pintype "bidirectional"))
    )
    (net (code "21") (name "ENCODER1_B") (class "Default")
      (node (ref "R15") (pin "2") (pinfunction "2_2") (pintype "passive"))
      (node (ref "U$3") (pin "PI5") (pinfunction "PI5_PI5") (pintype "bidirectional"))
    )
    (net (code "22") (name "ENCODER2_0") (class "Default")
      (node (ref "R35") (pin "2") (pinfunction "2_2") (pintype "passive"))
      (node (ref "U$3") (pin "PB5") (pinfunction "PB5_PB5") (pintype "bidirectional"))
    )
    (net (code "23") (name "ENCODER2_A") (class "Default")
      (node (ref "R24") (pin "2") (pinfunction "2_2") (pintype "passive"))
      (node (ref "U$3") (pin "PB3") (pinfunction "PB3_PB3") (pintype "bidirectional"))
    )
    (net (code "24") (name "ENCODER2_B") (class "Default")
      (node (ref "R62") (pin "2") (pinfunction "2_2") (pintype "passive"))
      (node (ref "U$3") (pin "PA0") (pinfunction "PA0_PA0") (pintype "bidirectional"))
    )
    (net (code "25") (name "ENCODER3_A") (class "Default")
      (node (ref "U$3") (pin "PC7") (pinfunction "PC7_PC7") (pintype "bidirectional"))
    )
    (net (code "26") (name "ENCODER3_B") (class "Default")
      (node (ref "U$3") (pin "PC6") (pinfunction "PC6_PC6") (pintype "bidirectional"))
    )
    (net (code "27") (name "ENCODER4_A") (class "Default")
      (node (ref "U$3") (pin "PD13") (pinfunction "PD13_PD13") (pintype "bidirectional"))
    )
    (net (code "28") (name "ENCODER4_B") (class "Default")
      (node (ref "U$3") (pin "PD12") (pinfunction "PD12_PD12") (pintype "bidirectional"))
    )
    (net (code "29") (name "ETH_CRS_DV") (class "Default")
      (node (ref "R41") (pin "2") (pinfunction "2_2") (pintype "passive"))
      (node (ref "U$3") (pin "PA7") (pinfunction "PA7_PA7") (pintype "bidirectional"))
    )
    (net (code "30") (name "ETH_LED1") (class "Default")
      (node (ref "J3") (pin "12") (pinfunction "12_12") (pintype "passive"))
      (node (ref "LAN8742A") (pin "3") (pinfunction "LED1/REGOFF_3") (pintype "bidirectional"))
    )
    (net (code "31") (name "ETH_LED2") (class "Default")
      (node (ref "J3") (pin "10") (pinfunction "10_10") (pintype "passive"))
      (node (ref "LAN8742A") (pin "2") (pinfunction "LED2/~{NINTSEL}_2") (pintype "bidirectional"))
      (node (ref "R53") (pin "2") (pinfunction "2_2") (pintype "passive"))
    )
    (net (code "32") (name "ETH_MDC") (class "Default")
      (node (ref "LAN8742A") (pin "13") (pinfunction "MDC_13") (pintype "input"))
      (node (ref "U$3") (pin "PC1") (pinfunction "PC1_PC1") (pintype "bidirectional"))
    )
    (net (code "33") (name "ETH_MDIO") (class "Default")
      (node (ref "LAN8742A") (pin "12") (pinfunction "MDIO_12") (pintype "bidirectional"))
      (node (ref "R54") (pin "2") (pinfunction "2_2") (pintype "passive"))
      (node (ref "U$3") (pin "PA2") (pinfunction "PA2_PA2") (pintype "bidirectional"))
    )
    (net (code "34") (name "ETH_REF_CLK") (class "Default")
      (node (ref "R48") (pin "2") (pinfunction "2_2") (pintype "passive"))
      (node (ref "U$3") (pin "PA1") (pinfunction "PA1_PA1") (pintype "bidirectional"))
    )
    (net (code "35") (name "ETH_RXD0") (class "Default")
      (node (ref "R38") (pin "2") (pinfunction "2_2") (pintype "passive"))
      (node (ref "U$3") (pin "PC4") (pinfunction "PC4_PC4") (pintype "bidirectional"))
    )
    (net (code "36") (name "ETH_RXD1") (class "Default")
      (node (ref "R37") (pin "2") (pinfunction "2_2") (pintype "passive"))
      (node (ref "U$3") (pin "PC5") (pinfunction "PC5_PC5") (pintype "bidirectional"))
    )
    (net (code "37") (name "ETH_TXD0") (class "Default")
      (node (ref "LAN8742A") (pin "17") (pinfunction "TXD0_17") (pintype "input"))
      (node (ref "U$3") (pin "PB12") (pinfunction "PB12_PB12") (pintype "bidirectional"))
    )
    (net (code "38") (name "ETH_TXD1") (class "Default")
      (node (ref "LAN8742A") (pin "18") (pinfunction "TXD1_18") (pintype "input"))
      (node (ref "U$3") (pin "PB13") (pinfunction "PB13_PB13") (pintype "bidirectional"))
    )
    (net (code "39") (name "ETH_TX_EN") (class "Default")
      (node (ref "LAN8742A") (pin "16") (pinfunction "TXEN_16") (pintype "input"))
      (node (ref "U$3") (pin "PB11") (pinfunction "PB11_PB11") (pintype "bidirectional"))
    )
    (net (code "40") (name "FLASH_CS") (class "Default")
      (node (ref "U$3") (pin "PA5") (pinfunction "PA5_PA5") (pintype "bidirectional"))
      (node (ref "U$4") (pin "7") (pinfunction "~{CS}_7") (pintype "bidirectional"))
    )
    (net (code "41") (name "FLASH_MISO") (class "Default")
      (node (ref "U$3") (pin "PC2") (pinfunction "PC2_PC2") (pintype "bidirectional"))
      (node (ref "U$4") (pin "8") (pinfunction "SO_8") (pintype "bidirectional"))
    )
    (net (code "42") (name "FLASH_MOSI") (class "Default")
      (node (ref "U$3") (pin "PC3") (pinfunction "PC3_PC3") (pintype "bidirectional"))
      (node (ref "U$4") (pin "15") (pinfunction "SI_15") (pintype "bidirectional"))
    )
    (net (code "43") (name "FLASH_SCK") (class "Default")
      (node (ref "U$3") (pin "PD3") (pinfunction "PD3_PD3") (pintype "bidirectional"))
      (node (ref "U$4") (pin "16") (pinfunction "SCK_16") (pintype "bidirectional"))
    )
    (net (code "44") (name "FMC_A0") (class "Default")
      (node (ref "U$1") (pin "23") (pinfunction "A0_23") (pintype "bidirectional"))
      (node (ref "U$3") (pin "PF0") (pinfunction "PF0_PF0") (pintype "bidirectional"))
    )
    (net (code "45") (name "FMC_A1") (class "Default")
      (node (ref "U$1") (pin "24") (pinfunction "A1_24") (pintype "bidirectional"))
      (node (ref "U$3") (pin "PF1") (pinfunction "PF1_PF1") (pintype "bidirectional"))
    )
    (net (code "46") (name "FMC_A2") (class "Default")
      (node (ref "U$1") (pin "25") (pinfunction "A2_25") (pintype "bidirectional"))
      (node (ref "U$3") (pin "PF2") (pinfunction "PF2_PF2") (pintype "bidirectional"))
    )
    (net (code "47") (name "FMC_A3") (class "Default")
      (node (ref "U$1") (pin "26") (pinfunction "A3_26") (pintype "bidirectional"))
      (node (ref "U$3") (pin "PF3") (pinfunction "PF3_PF3") (pintype "bidirectional"))
    )
    (net (code "48") (name "FMC_A4") (class "Default")
      (node (ref "U$1") (pin "29") (pinfunction "A4_29") (pintype "bidirectional"))
      (node (ref "U$3") (pin "PF4") (pinfunction "PF4_PF4") (pintype "bidirectional"))
    )
    (net (code "49") (name "FMC_A5") (class "Default")
      (node (ref "U$1") (pin "30") (pinfunction "A5_30") (pintype "bidirectional"))
      (node (ref "U$3") (pin "PF5") (pinfunction "PF5_PF5") (pintype "bidirectional"))
    )
    (net (code "50") (name "FMC_A6") (class "Default")
      (node (ref "U$1") (pin "31") (pinfunction "A6_31") (pintype "bidirectional"))
      (node (ref "U$3") (pin "PF12") (pinfunction "PF12_PF12") (pintype "bidirectional"))
    )
    (net (code "51") (name "FMC_A7") (class "Default")
      (node (ref "U$1") (pin "32") (pinfunction "A7_32") (pintype "bidirectional"))
      (node (ref "U$3") (pin "PF13") (pinfunction "PF13_PF13") (pintype "bidirectional"))
    )
    (net (code "52") (name "FMC_A8") (class "Default")
      (node (ref "U$1") (pin "33") (pinfunction "A8_33") (pintype "bidirectional"))
      (node (ref "U$3") (pin "PF14") (pinfunction "PF14_PF14") (pintype "bidirectional"))
    )
    (net (code "53") (name "FMC_A9") (class "Default")
      (node (ref "U$1") (pin "34") (pinfunction "A9_34") (pintype "bidirectional"))
      (node (ref "U$3") (pin "PF15") (pinfunction "PF15_PF15") (pintype "bidirectional"))
    )
    (net (code "54") (name "FMC_A10") (class "Default")
      (node (ref "U$1") (pin "22") (pinfunction "A10_22") (pintype "bidirectional"))
      (node (ref "U$3") (pin "PG0") (pinfunction "PG0_PG0") (pintype "bidirectional"))
    )
    (net (code "55") (name "FMC_A11") (class "Default")
      (node (ref "U$1") (pin "35") (pinfunction "A11_35") (pintype "bidirectional"))
      (node (ref "U$3") (pin "PG1") (pinfunction "PG1_PG1") (pintype "bidirectional"))
    )
    (net (code "56") (name "FMC_BA0") (class "Default")
      (node (ref "U$1") (pin "20") (pinfunction "BA0_20") (pintype "bidirectional"))
      (node (ref "U$3") (pin "PG4") (pinfunction "PG4_PG4") (pintype "bidirectional"))
    )
    (net (code "57") (name "FMC_BA1") (class "Default")
      (node (ref "U$1") (pin "21") (pinfunction "BA1_21") (pintype "bidirectional"))
      (node (ref "U$3") (pin "PG5") (pinfunction "PG5_PG5") (pintype "bidirectional"))
    )
    (net (code "58") (name "FMC_D0") (class "Default")
      (node (ref "U$1") (pin "2") (pinfunction "D0_2") (pintype "bidirectional"))
      (node (ref "U$3") (pin "PD14") (pinfunction "PD14_PD14") (pintype "bidirectional"))
    )
    (net (code "59") (name "FMC_D1") (class "Default")
      (node (ref "U$1") (pin "4") (pinfunction "D1_4") (pintype "bidirectional"))
      (node (ref "U$3") (pin "PD15") (pinfunction "PD15_PD15") (pintype "bidirectional"))
    )
    (net (code "60") (name "FMC_D2") (class "Default")
      (node (ref "U$1") (pin "5") (pinfunction "D2_5") (pintype "bidirectional"))
      (node (ref "U$3") (pin "PD0") (pinfunction "PD0_PD0") (pintype "bidirectional"))
    )
    (net (code "61") (name "FMC_D3") (class "Default")
      (node (ref "U$1") (pin "7") (pinfunction "D3_7") (pintype "bidirectional"))
      (node (ref "U$3") (pin "PD1") (pinfunction "PD1_PD1") (pintype "bidirectional"))
    )
    (net (code "62") (name "FMC_D4") (class "Default")
      (node (ref "U$1") (pin "8") (pinfunction "D4_8") (pintype "bidirectional"))
      (node (ref "U$3") (pin "PE7") (pinfunction "PE7_PE7") (pintype "bidirectional"))
    )
    (net (code "63") (name "FMC_D5") (class "Default")
      (node (ref "U$1") (pin "10") (pinfunction "D5_10") (pintype "bidirectional"))
      (node (ref "U$3") (pin "PE8") (pinfunction "PE8_PE8") (pintype "bidirectional"))
    )
    (net (code "64") (name "FMC_D6") (class "Default")
      (node (ref "U$1") (pin "11") (pinfunction "D6_11") (pintype "bidirectional"))
      (node (ref "U$3") (pin "PE9") (pinfunction "PE9_PE9") (pintype "bidirectional"))
    )
    (net (code "65") (name "FMC_D7") (class "Default")
      (node (ref "U$1") (pin "13") (pinfunction "D7_13") (pintype "bidirectional"))
      (node (ref "U$3") (pin "PE10") (pinfunction "PE10_PE10") (pintype "bidirectional"))
    )
    (net (code "66") (name "FMC_D8") (class "Default")
      (node (ref "U$1") (pin "42") (pinfunction "D8_42") (pintype "bidirectional"))
      (node (ref "U$3") (pin "PE11") (pinfunction "PE11_PE11") (pintype "bidirectional"))
    )
    (net (code "67") (name "FMC_D9") (class "Default")
      (node (ref "U$1") (pin "44") (pinfunction "D9_44") (pintype "bidirectional"))
      (node (ref "U$3") (pin "PE12") (pinfunction "PE12_PE12") (pintype "bidirectional"))
    )
    (net (code "68") (name "FMC_D10") (class "Default")
      (node (ref "U$1") (pin "45") (pinfunction "D10_45") (pintype "bidirectional"))
      (node (ref "U$3") (pin "PE13") (pinfunction "PE13_PE13") (pintype "bidirectional"))
    )
    (net (code "69") (name "FMC_D11") (class "Default")
      (node (ref "U$1") (pin "47") (pinfunction "D11_47") (pintype "bidirectional"))
      (node (ref "U$3") (pin "PE14") (pinfunction "PE14_PE14") (pintype "bidirectional"))
    )
    (net (code "70") (name "FMC_D12") (class "Default")
      (node (ref "U$1") (pin "48") (pinfunction "D12_48") (pintype "bidirectional"))
      (node (ref "U$3") (pin "PE15") (pinfunction "PE15_PE15") (pintype "bidirectional"))
    )
    (net (code "71") (name "FMC_D13") (class "Default")
      (node (ref "U$1") (pin "50") (pinfunction "D13_50") (pintype "bidirectional"))
      (node (ref "U$3") (pin "PD8") (pinfunction "PD8_PD8") (pintype "bidirectional"))
    )
    (net (code "72") (name "FMC_D14") (class "Default")
      (node (ref "U$1") (pin "51") (pinfunction "D14_51") (pintype "bidirectional"))
      (node (ref "U$3") (pin "PD9") (pinfunction "PD9_PD9") (pintype "bidirectional"))
    )
    (net (code "73") (name "FMC_D15") (class "Default")
      (node (ref "U$1") (pin "53") (pinfunction "D15_53") (pintype "bidirectional"))
      (node (ref "U$3") (pin "PD10") (pinfunction "PD10_PD10") (pintype "bidirectional"))
    )
    (net (code "74") (name "FMC_NBL0") (class "Default")
      (node (ref "U$1") (pin "15") (pinfunction "LDQM_15") (pintype "bidirectional"))
      (node (ref "U$3") (pin "PE0") (pinfunction "PE0_PE0") (pintype "bidirectional"))
    )
    (net (code "75") (name "FMC_NBL1") (class "Default")
      (node (ref "U$1") (pin "39") (pinfunction "UDQM_39") (pintype "bidirectional"))
      (node (ref "U$3") (pin "PE1") (pinfunction "PE1_PE1") (pintype "bidirectional"))
    )
    (net (code "76") (name "FMC_SDCKE1") (class "Default")
      (node (ref "U$1") (pin "37") (pinfunction "CKE_37") (pintype "bidirectional"))
      (node (ref "U$3") (pin "PH7") (pinfunction "PH7_PH7") (pintype "bidirectional"))
    )
    (net (code "77") (name "FMC_SDCLK") (class "Default")
      (node (ref "U$1") (pin "38") (pinfunction "CLK_38") (pintype "bidirectional"))
      (node (ref "U$3") (pin "PG8") (pinfunction "PG8_PG8") (pintype "bidirectional"))
    )
    (net (code "78") (name "FMC_SDNCAS") (class "Default")
      (node (ref "U$1") (pin "17") (pinfunction "~{CAS}_17") (pintype "bidirectional"))
      (node (ref "U$3") (pin "PG15") (pinfunction "PG15_PG15") (pintype "bidirectional"))
    )
    (net (code "79") (name "FMC_SDNE1") (class "Default")
      (node (ref "U$1") (pin "19") (pinfunction "~{CS}_19") (pintype "bidirectional"))
      (node (ref "U$3") (pin "PH6") (pinfunction "PH6_PH6") (pintype "bidirectional"))
    )
    (net (code "80") (name "FMC_SDNRAS") (class "Default")
      (node (ref "U$1") (pin "18") (pinfunction "~{RAS}_18") (pintype "bidirectional"))
      (node (ref "U$3") (pin "PF11") (pinfunction "PF11_PF11") (pintype "bidirectional"))
    )
    (net (code "81") (name "FMC_SDNWE") (class "Default")
      (node (ref "U$1") (pin "16") (pinfunction "~{WE}_16") (pintype "bidirectional"))
      (node (ref "U$3") (pin "PC0") (pinfunction "PC0_PC0") (pintype "bidirectional"))
    )
    (net (code "82") (name "GND") (class "Default")
      (node (ref "BT1") (pin "2") (pinfunction "-_2") (pintype "passive"))
      (node (ref "C10") (pin "2") (pinfunction "2_2") (pintype "passive"))
      (node (ref "C11") (pin "2") (pinfunction "2_2") (pintype "passive"))
      (node (ref "C14") (pin "2") (pinfunction "2_2") (pintype "passive"))
      (node (ref "C19") (pin "2") (pinfunction "2_2") (pintype "passive"))
      (node (ref "C20") (pin "2") (pinfunction "2_2") (pintype "passive"))
      (node (ref "C21") (pin "2") (pinfunction "2_2") (pintype "passive"))
      (node (ref "C22") (pin "2") (pinfunction "2_2") (pintype "passive"))
      (node (ref "C23") (pin "2") (pinfunction "2_2") (pintype "passive"))
      (node (ref "C24") (pin "2") (pinfunction "2_2") (pintype "passive"))
      (node (ref "C25") (pin "2") (pinfunction "2_2") (pintype "passive"))
      (node (ref "C26") (pin "2") (pinfunction "2_2") (pintype "passive"))
      (node (ref "C27") (pin "2") (pinfunction "2_2") (pintype "passive"))
      (node (ref "C28") (pin "2") (pinfunction "2_2") (pintype "passive"))
      (node (ref "C29") (pin "2") (pinfunction "2_2") (pintype "passive"))
      (node (ref "C30") (pin "2") (pinfunction "2_2") (pintype "passive"))
      (node (ref "C31") (pin "2") (pinfunction "2_2") (pintype "passive"))
      (node (ref "C32") (pin "2") (pinfunction "2_2") (pintype "passive"))
      (node (ref "C33") (pin "2") (pinfunction "2_2") (pintype "passive"))
      (node (ref "C38") (pin "2") (pinfunction "2_2") (pintype "passive"))
      (node (ref "C39") (pin "2") (pinfunction "2_2") (pintype "passive"))
      (node (ref "C40") (pin "2") (pinfunction "2_2") (pintype "passive"))
      (node (ref "C41") (pin "2") (pinfunction "2_2") (pintype "passive"))
      (node (ref "C42") (pin "2") (pinfunction "2_2") (pintype "passive"))
      (node (ref "C43") (pin "2") (pinfunction "2_2") (pintype "passive"))
      (node (ref "C44") (pin "2") (pinfunction "2_2") (pintype "passive"))
      (node (ref "C45") (pin "2") (pinfunction "2_2") (pintype "passive"))
      (node (ref "C46") (pin "2") (pinfunction "2_2") (pintype "passive"))
      (node (ref "C47") (pin "2") (pinfunction "2_2") (pintype "passive"))
      (node (ref "C48") (pin "2") (pinfunction "2_2") (pintype "passive"))
      (node (ref "C50") (pin "2") (pinfunction "2_2") (pintype "passive"))
      (node (ref "C51") (pin "2") (pinfunction "2_2") (pintype "passive"))
      (node (ref "C52") (pin "2") (pinfunction "2_2") (pintype "passive"))
      (node (ref "C53") (pin "2") (pinfunction "2_2") (pintype "passive"))
      (node (ref "C54") (pin "2") (pinfunction "2_2") (pintype "passive"))
      (node (ref "C55") (pin "2") (pinfunction "2_2") (pintype "passive"))
      (node (ref "C57") (pin "2") (pinfunction "2_2") (pintype "passive"))
      (node (ref "C58") (pin "2") (pinfunction "2_2") (pintype "passive"))
      (node (ref "C59") (pin "2") (pinfunction "2_2") (pintype "passive"))
      (node (ref "C60") (pin "2") (pinfunction "2_2") (pintype "passive"))
      (node (ref "C61") (pin "2") (pinfunction "2_2") (pintype "passive"))
      (node (ref "C62") (pin "2") (pinfunction "2_2") (pintype "passive"))
      (node (ref "C63") (pin "-") (pinfunction "-_-") (pintype "passive"))
      (node (ref "C64") (pin "2") (pinfunction "2_2") (pintype "passive"))
      (node (ref "C65") (pin "2") (pinfunction "2_2") (pintype "passive"))
      (node (ref "C66") (pin "2") (pinfunction "2_2") (pintype "passive"))
      (node (ref "C67") (pin "2") (pinfunction "2_2") (pintype "passive"))
      (node (ref "C68") (pin "2") (pinfunction "2_2") (pintype "passive"))
      (node (ref "C69") (pin "2") (pinfunction "2_2") (pintype "passive"))
      (node (ref "C70") (pin "2") (pinfunction "2_2") (pintype "passive"))
      (node (ref "C71") (pin "2") (pinfunction "2_2") (pintype "passive"))
      (node (ref "C72") (pin "2") (pinfunction "2_2") (pintype "passive"))
      (node (ref "C84") (pin "2") (pinfunction "2_2") (pintype "passive"))
      (node (ref "C85") (pin "2") (pinfunction "2_2") (pintype "passive"))
      (node (ref "C86") (pin "2") (pinfunction "2_2") (pintype "passive"))
      (node (ref "C87") (pin "2") (pinfunction "2_2") (pintype "passive"))
      (node (ref "C89") (pin "2") (pinfunction "2_2") (pintype "passive"))
      (node (ref "C9") (pin "2") (pinfunction "2_2") (pintype "passive"))
      (node (ref "C91") (pin "-") (pinfunction "-_-") (pintype "passive"))
      (node (ref "C92") (pin "2") (pinfunction "2_2") (pintype "passive"))
      (node (ref "C93") (pin "2") (pinfunction "2_2") (pintype "passive"))
      (node (ref "C94") (pin "2") (pinfunction "2_2") (pintype "passive"))
      (node (ref "D1") (pin "A") (pinfunction "A_A") (pintype "passive"))
      (node (ref "ESDA6V1BC6") (pin "2") (pinfunction "2_2") (pintype "passive"))
      (node (ref "ESDA6V1BC6") (pin "5") (pinfunction "5_5") (pintype "passive"))
      (node (ref "JP10") (pin "1") (pinfunction "1_1") (pintype "passive"))
      (node (ref "JP6") (pin "1") (pinfunction "1_1") (pintype "passive"))
      (node (ref "JP7") (pin "1") (pinfunction "1_1") (pintype "passive"))
      (node (ref "JP8") (pin "1") (pinfunction "1_1") (pintype "passive"))
      (node (ref "JP9") (pin "1") (pinfunction "1_1") (pintype "passive"))
      (node (ref "LAN8742A") (pin "25") (pinfunction "VSS_25") (pintype "power_in"))
      (node (ref "R1") (pin "1") (pinfunction "1_1") (pintype "passive"))
      (node (ref "R19") (pin "1") (pinfunction "1_1") (pintype "passive"))
      (node (ref "R2") (pin "1") (pinfunction "1_1") (pintype "passive"))
      (node (ref "R21") (pin "1") (pinfunction "1_1") (pintype "passive"))
      (node (ref "R22") (pin "2") (pinfunction "2_2") (pintype "passive"))
      (node (ref "R3") (pin "1") (pinfunction "1_1") (pintype "passive"))
      (node (ref "R34") (pin "1") (pinfunction "1_1") (pintype "passive"))
      (node (ref "R43") (pin "1") (pinfunction "1_1") (pintype "passive"))
      (node (ref "R50") (pin "2") (pinfunction "2_2") (pintype "passive"))
      (node (ref "R51") (pin "1") (pinfunction "1_1") (pintype "passive"))
      (node (ref "R52") (pin "1") (pinfunction "1_1") (pintype "passive"))
      (node (ref "R53") (pin "1") (pinfunction "1_1") (pintype "passive"))
      (node (ref "R69") (pin "1") (pinfunction "1_1") (pintype "passive"))
      (node (ref "R70") (pin "1") (pinfunction "1_1") (pintype "passive"))
      (node (ref "R71") (pin "1") (pinfunction "1_1") (pintype "passive"))
      (node (ref "R9") (pin "2") (pinfunction "2_2") (pintype "passive"))
      (node (ref "S1") (pin "1") (pinfunction "1_1") (pintype "passive"))
      (node (ref "S1") (pin "4") (pinfunction "1_4") (pintype "passive"))
      (node (ref "SJ2") (pin "1") (pinfunction "1_1") (pintype "passive"))
      (node (ref "SJ3") (pin "1") (pinfunction "1_1") (pintype "passive"))
      (node (ref "U$1") (pin "12") (pinfunction "GNDQ_12") (pintype "bidirectional"))
      (node (ref "U$1") (pin "28") (pinfunction "GND_28") (pintype "bidirectional"))
      (node (ref "U$1") (pin "41") (pinfunction "GND_41") (pintype "bidirectional"))
      (node (ref "U$1") (pin "46") (pinfunction "GNDQ_46") (pintype "bidirectional"))
      (node (ref "U$1") (pin "52") (pinfunction "GNDQ_52") (pintype "bidirectional"))
      (node (ref "U$1") (pin "54") (pinfunction "GND_54") (pintype "bidirectional"))
      (node (ref "U$1") (pin "6") (pinfunction "GNDQ_6") (pintype "bidirectional"))
      (node (ref "U$10") (pin "1") (pinfunction "P$1_1") (pintype "bidirectional"))
      (node (ref "U$11") (pin "1") (pinfunction "P$1_1") (pintype "bidirectional"))
      (node (ref "U$12") (pin "1") (pinfunction "P$1_1") (pintype "bidirectional"))
      (node (ref "U$13") (pin "1") (pinfunction "P$1_1") (pintype "bidirectional"))
      (node (ref "U$14") (pin "1") (pinfunction "P$1_1") (pintype "bidirectional"))
      (node (ref "U$15") (pin "1") (pinfunction "P$1_1") (pintype "bidirectional"))
      (node (ref "U$16") (pin "1") (pinfunction "P$1_1") (pintype "bidirectional"))
      (node (ref "U$17") (pin "1") (pinfunction "P$1_1") (pintype "bidirectional"))
      (node (ref "U$3") (pin "BYPASS_REG") (pinfunction "BYPASS_REG_BYPASS_REG") (pintype "bidirectional"))
      (node (ref "U$3") (pin "VSS@1") (pinfunction "VSS_VSS@1") (pintype "bidirectional"))
      (node (ref "U$3") (pin "VSS@10") (pinfunction "VSS_VSS@10") (pintype "bidirectional"))
      (node (ref "U$3") (pin "VSS@11") (pinfunction "VSS_VSS@11") (pintype "bidirectional"))
      (node (ref "U$3") (pin "VSS@12") (pinfunction "VSS_VSS@12") (pintype "bidirectional"))
      (node (ref "U$3") (pin "VSS@2") (pinfunction "VSS_VSS@2") (pintype "bidirectional"))
      (node (ref "U$3") (pin "VSS@3") (pinfunction "VSS_VSS@3") (pintype "bidirectional"))
      (node (ref "U$3") (pin "VSS@4") (pinfunction "VSS_VSS@4") (pintype "bidirectional"))
      (node (ref "U$3") (pin "VSS@5") (pinfunction "VSS_VSS@5") (pintype "bidirectional"))
      (node (ref "U$3") (pin "VSS@7") (pinfunction "VSS_VSS@7") (pintype "bidirectional"))
      (node (ref "U$3") (pin "VSS@8") (pinfunction "VSS_VSS@8") (pintype "bidirectional"))
      (node (ref "U$3") (pin "VSS@9") (pinfunction "VSS_VSS@9") (pintype "bidirectional"))
      (node (ref "U$4") (pin "10") (pinfunction "VSS_10") (pintype "bidirectional"))
      (node (ref "U$5") (pin "6") (pinfunction "6_6") (pintype "passive"))
      (node (ref "U$6") (pin "1") (pinfunction "P$1_1") (pintype "bidirectional"))
      (node (ref "U$8") (pin "1") (pinfunction "P$1_1") (pintype "bidirectional"))
      (node (ref "U$9") (pin "1") (pinfunction "P$1_1") (pintype "bidirectional"))
      (node (ref "U3") (pin "2") (pinfunction "GND_2") (pintype "passive"))
      (node (ref "U3") (pin "4") (pinfunction "GND2_4") (pintype "passive"))
      (node (ref "U4") (pin "2") (pinfunction "GND_2") (pintype "power_in"))
      (node (ref "U5") (pin "2") (pinfunction "GND_2") (pintype "passive"))
      (node (ref "U5") (pin "4") (pinfunction "GND2_4") (pintype "passive"))
      (node (ref "U6") (pin "10") (pinfunction "EXP_10") (pintype "power_in"))
      (node (ref "U6") (pin "11") (pinfunction "EXP_11") (pintype "power_in"))
      (node (ref "U6") (pin "12") (pinfunction "EXP_12") (pintype "power_in"))
      (node (ref "U6") (pin "13") (pinfunction "EXP_13") (pintype "power_in"))
      (node (ref "U6") (pin "14") (pinfunction "EXP_14") (pintype "power_in"))
      (node (ref "U6") (pin "15") (pinfunction "EXP_15") (pintype "power_in"))
      (node (ref "U6") (pin "7") (pinfunction "GND_7") (pintype "power_in"))
      (node (ref "U6") (pin "9") (pinfunction "EXP_9") (pintype "power_in"))
      (node (ref "X1") (pin "29") (pinfunction "1_29") (pintype "passive"))
      (node (ref "X1") (pin "3") (pinfunction "1_3") (pintype "passive"))
      (node (ref "X1") (pin "36") (pinfunction "1_36") (pintype "passive"))
      (node (ref "X4") (pin "5") (pinfunction "5_5") (pintype "passive"))
      (node (ref "Y1") (pin "2") (pinfunction "GND_2") (pintype "power_in"))
      (node (ref "Y1") (pin "4") (pinfunction "GND_4") (pintype "power_in"))
    )
    (net (code "83") (name "GNDA") (class "Default")
      (node (ref "C1") (pin "2") (pinfunction "2_2") (pintype "passive"))
      (node (ref "C12") (pin "2") (pinfunction "2_2") (pintype "passive"))
      (node (ref "C13") (pin "2") (pinfunction "2_2") (pintype "passive"))
      (node (ref "C15") (pin "2") (pinfunction "2_2") (pintype "passive"))
      (node (ref "C16") (pin "2") (pinfunction "2_2") (pintype "passive"))
      (node (ref "C2") (pin "2") (pinfunction "2_2") (pintype "passive"))
      (node (ref "C34") (pin "2") (pinfunction "2_2") (pintype "passive"))
      (node (ref "C35") (pin "2") (pinfunction "2_2") (pintype "passive"))
      (node (ref "C36") (pin "2") (pinfunction "2_2") (pintype "passive"))
      (node (ref "C37") (pin "2") (pinfunction "2_2") (pintype "passive"))
      (node (ref "C4") (pin "2") (pinfunction "2_2") (pintype "passive"))
      (node (ref "C49") (pin "1") (pinfunction "1_1") (pintype "passive"))
      (node (ref "C5") (pin "2") (pinfunction "2_2") (pintype "passive"))
      (node (ref "C56") (pin "1") (pinfunction "1_1") (pintype "passive"))
      (node (ref "C6") (pin "2") (pinfunction "2_2") (pintype "passive"))
      (node (ref "C7") (pin "2") (pinfunction "2_2") (pintype "passive"))
      (node (ref "C8") (pin "2") (pinfunction "2_2") (pintype "passive"))
      (node (ref "JP4") (pin "3") (pinfunction "3_3") (pintype "passive"))
      (node (ref "R1") (pin "2") (pinfunction "2_2") (pintype "passive"))
      (node (ref "R11") (pin "1") (pinfunction "1_1") (pintype "passive"))
      (node (ref "R7") (pin "1") (pinfunction "1_1") (pintype "passive"))
      (node (ref "RSET") (pin "1") (pinfunction "1_1") (pintype "passive"))
      (node (ref "U$2") (pin "6") (pinfunction "GND_6") (pintype "bidirectional"))
      (node (ref "U$2") (pin "E") (pinfunction "GND_E") (pintype "bidirectional"))
      (node (ref "U$3") (pin "VSSA") (pinfunction "VSSA_VSSA") (pintype "bidirectional"))
      (node (ref "U1") (pin "1") (pinfunction "GND_1") (pintype "power_in"))
      (node (ref "U1") (pin "12") (pinfunction "GND_12") (pintype "power_in"))
      (node (ref "U1") (pin "15") (pinfunction "GND_15") (pintype "power_in"))
      (node (ref "U1") (pin "3") (pinfunction "GND_3") (pintype "power_in"))
      (node (ref "U1") (pin "36") (pinfunction "COM_36") (pintype "input"))
      (node (ref "U1") (pin "44") (pinfunction "GND_44") (pintype "power_in"))
      (node (ref "U1") (pin "5") (pinfunction "GND_5") (pintype "power_in"))
      (node (ref "U1") (pin "7") (pinfunction "GND_7") (pintype "power_in"))
      (node (ref "U1") (pin "9") (pinfunction "GND_9") (pintype "power_in"))
      (node (ref "U2") (pin "10") (pinfunction "GND_10") (pintype "passive"))
      (node (ref "U2") (pin "11") (pinfunction "EP_11") (pintype "passive"))
    )
    (net (code "84") (name "IOUT") (class "Default")
      (node (ref "C7") (pin "1") (pinfunction "1_1") (pintype "passive"))
      (node (ref "JP4") (pin "2") (pinfunction "2_2") (pintype "passive"))
      (node (ref "R5") (pin "2") (pinfunction "2_2") (pintype "passive"))
    )
    (net (code "85") (name "IS") (class "Default")
      (node (ref "Q2") (pin "E") (pinfunction "E_E") (pintype "passive"))
      (node (ref "R4") (pin "1") (pinfunction "1_1") (pintype "passive"))
      (node (ref "U2") (pin "2") (pinfunction "IS_2") (pintype "input"))
    )
    (net (code "86") (name "LCD_BL_ADJ") (class "Default")
      (node (ref "C58") (pin "1") (pinfunction "1_1") (pintype "passive"))
      (node (ref "R26") (pin "1") (pinfunction "1_1") (pintype "passive"))
      (node (ref "X1") (pin "35") (pinfunction "1_35") (pintype "passive"))
    )
    (net (code "87") (name "LTC_CS") (class "Default")
      (node (ref "R29") (pin "2") (pinfunction "2_2") (pintype "passive"))
      (node (ref "U$3") (pin "PE3") (pinfunction "PE3_PE3") (pintype "bidirectional"))
    )
    (net (code "88") (name "LTC_IT") (class "Default")
      (node (ref "R31") (pin "1") (pinfunction "1_1") (pintype "passive"))
      (node (ref "U$3") (pin "PI7") (pinfunction "PI7_PI7") (pintype "bidirectional"))
    )
    (net (code "89") (name "LTC_MISO") (class "Default")
      (node (ref "R27") (pin "2") (pinfunction "2_2") (pintype "passive"))
      (node (ref "U$3") (pin "PE5") (pinfunction "PE5_PE5") (pintype "bidirectional"))
    )
    (net (code "90") (name "LTC_MOSI") (class "Default")
      (node (ref "R") (pin "2") (pinfunction "2_2") (pintype "passive"))
      (node (ref "U$3") (pin "PE6") (pinfunction "PE6_PE6") (pintype "bidirectional"))
    )
    (net (code "91") (name "LTC_RESET") (class "Default")
      (node (ref "R30") (pin "2") (pinfunction "2_2") (pintype "passive"))
      (node (ref "U$3") (pin "PE4") (pinfunction "PE4_PE4") (pintype "bidirectional"))
    )
    (net (code "92") (name "LTC_SCK") (class "Default")
      (node (ref "R28") (pin "2") (pinfunction "2_2") (pintype "passive"))
      (node (ref "U$3") (pin "PE2") (pinfunction "PE2_PE2") (pintype "bidirectional"))
    )
    (net (code "93") (name "LTDC_B0") (class "Default")
      (node (ref "X1") (pin "21") (pinfunction "1_21") (pintype "passive"))
    )
    (net (code "94") (name "LTDC_B1") (class "Default")
      (node (ref "X1") (pin "22") (pinfunction "1_22") (pintype "passive"))
    )
    (net (code "95") (name "LTDC_B2") (class "Default")
      (node (ref "U$3") (pin "PD6") (pinfunction "PD6_PD6") (pintype "bidirectional"))
      (node (ref "X1") (pin "23") (pinfunction "1_23") (pintype "passive"))
    )
    (net (code "96") (name "LTDC_B3") (class "Default")
      (node (ref "U$3") (pin "PG11") (pinfunction "PG11_PG11") (pintype "bidirectional"))
      (node (ref "X1") (pin "24") (pinfunction "1_24") (pintype "passive"))
    )
    (net (code "97") (name "LTDC_B4") (class "Default")
      (node (ref "U$3") (pin "PG12") (pinfunction "PG12_PG12") (pintype "bidirectional"))
      (node (ref "X1") (pin "25") (pinfunction "1_25") (pintype "passive"))
    )
    (net (code "98") (name "LTDC_B5") (class "Default")
      (node (ref "U$3") (pin "PA3") (pinfunction "PA3_PA3") (pintype "bidirectional"))
      (node (ref "X1") (pin "26") (pinfunction "1_26") (pintype "passive"))
    )
    (net (code "99") (name "LTDC_B6") (class "Default")
      (node (ref "U$3") (pin "PB8") (pinfunction "PB8_PB8") (pintype "bidirectional"))
      (node (ref "X1") (pin "27") (pinfunction "1_27") (pintype "passive"))
    )
    (net (code "100") (name "LTDC_B7") (class "Default")
      (node (ref "U$3") (pin "PB9") (pinfunction "PB9_PB9") (pintype "bidirectional"))
      (node (ref "X1") (pin "28") (pinfunction "1_28") (pintype "passive"))
    )
    (net (code "101") (name "LTDC_DE") (class "Default")
      (node (ref "U$3") (pin "PF10") (pinfunction "PF10_PF10") (pintype "bidirectional"))
      (node (ref "X1") (pin "34") (pinfunction "1_34") (pintype "passive"))
    )
    (net (code "102") (name "LTDC_G0") (class "Default")
      (node (ref "X1") (pin "13") (pinfunction "1_13") (pintype "passive"))
    )
    (net (code "103") (name "LTDC_G1") (class "Default")
      (node (ref "X1") (pin "14") (pinfunction "1_14") (pintype "passive"))
    )
    (net (code "104") (name "LTDC_G2") (class "Default")
      (node (ref "U$3") (pin "PH13") (pinfunction "PH13_PH13") (pintype "bidirectional"))
      (node (ref "X1") (pin "15") (pinfunction "1_15") (pintype "passive"))
    )
    (net (code "105") (name "LTDC_G3") (class "Default")
      (node (ref "U$3") (pin "PH14") (pinfunction "PH14_PH14") (pintype "bidirectional"))
      (node (ref "X1") (pin "16") (pinfunction "1_16") (pintype "passive"))
    )
    (net (code "106") (name "LTDC_G4") (class "Default")
      (node (ref "U$3") (pin "PB10") (pinfunction "PB10_PB10") (pintype "bidirectional"))
      (node (ref "X1") (pin "17") (pinfunction "1_17") (pintype "passive"))
    )
    (net (code "107") (name "LTDC_G5") (class "Default")
      (node (ref "U$3") (pin "PI0") (pinfunction "PI0_PI0") (pintype "bidirectional"))
      (node (ref "X1") (pin "18") (pinfunction "1_18") (pintype "passive"))
    )
    (net (code "108") (name "LTDC_G6") (class "Default")
      (node (ref "U$3") (pin "PI1") (pinfunction "PI1_PI1") (pintype "bidirectional"))
      (node (ref "X1") (pin "19") (pinfunction "1_19") (pintype "passive"))
    )
    (net (code "109") (name "LTDC_G7") (class "Default")
      (node (ref "U$3") (pin "PI2") (pinfunction "PI2_PI2") (pintype "bidirectional"))
      (node (ref "X1") (pin "20") (pinfunction "1_20") (pintype "passive"))
    )
    (net (code "110") (name "LTDC_HSYNC") (class "Default")
      (node (ref "U$3") (pin "PI10") (pinfunction "PI10_PI10") (pintype "bidirectional"))
      (node (ref "X1") (pin "32") (pinfunction "1_32") (pintype "passive"))
    )
    (net (code "111") (name "LTDC_PCLK") (class "Default")
      (node (ref "U$3") (pin "PG7") (pinfunction "PG7_PG7") (pintype "bidirectional"))
      (node (ref "X1") (pin "30") (pinfunction "1_30") (pintype "passive"))
    )
    (net (code "112") (name "LTDC_R0") (class "Default")
      (node (ref "X1") (pin "5") (pinfunction "1_5") (pintype "passive"))
    )
    (net (code "113") (name "LTDC_R1") (class "Default")
      (node (ref "X1") (pin "6") (pinfunction "1_6") (pintype "passive"))
    )
    (net (code "114") (name "LTDC_R2") (class "Default")
      (node (ref "U$3") (pin "PH8") (pinfunction "PH8_PH8") (pintype "bidirectional"))
      (node (ref "X1") (pin "7") (pinfunction "1_7") (pintype "passive"))
    )
    (net (code "115") (name "LTDC_R3") (class "Default")
      (node (ref "U$3") (pin "PB0") (pinfunction "PB0_PB0") (pintype "bidirectional"))
      (node (ref "X1") (pin "8") (pinfunction "1_8") (pintype "passive"))
    )
    (net (code "116") (name "LTDC_R4") (class "Default")
      (node (ref "U$3") (pin "PH10") (pinfunction "PH10_PH10") (pintype "bidirectional"))
      (node (ref "X1") (pin "9") (pinfunction "1_9") (pintype "passive"))
    )
    (net (code "117") (name "LTDC_R5") (class "Default")
      (node (ref "U$3") (pin "PH11") (pinfunction "PH11_PH11") (pintype "bidirectional"))
      (node (ref "X1") (pin "10") (pinfunction "1_10") (pintype "passive"))
    )
    (net (code "118") (name "LTDC_R6") (class "Default")
      (node (ref "U$3") (pin "PB1") (pinfunction "PB1_PB1") (pintype "bidirectional"))
      (node (ref "X1") (pin "11") (pinfunction "1_11") (pintype "passive"))
    )
    (net (code "119") (name "LTDC_R7") (class "Default")
      (node (ref "U$3") (pin "PG6") (pinfunction "PG6_PG6") (pintype "bidirectional"))
      (node (ref "X1") (pin "12") (pinfunction "1_12") (pintype "passive"))
    )
    (net (code "120") (name "LTDC_VSYNC") (class "Default")
      (node (ref "U$3") (pin "PI9") (pinfunction "PI9_PI9") (pintype "bidirectional"))
      (node (ref "X1") (pin "33") (pinfunction "1_33") (pintype "passive"))
    )
    (net (code "121") (name "NRST") (class "Default")
      (node (ref "C59") (pin "1") (pinfunction "1_1") (pintype "passive"))
      (node (ref "R49") (pin "1") (pinfunction "1_1") (pintype "passive"))
      (node (ref "S1") (pin "2") (pinfunction "3_2") (pintype "passive"))
      (node (ref "S1") (pin "3") (pinfunction "3_3") (pintype "passive"))
      (node (ref "U$3") (pin "NRST") (pinfunction "NRST_NRST") (pintype "bidirectional"))
      (node (ref "U$5") (pin "5") (pinfunction "5_5") (pintype "passive"))
    )
    (net (code "122") (name "Net-(C18-Pad2)") (class "Default")
      (node (ref "C18") (pin "2") (pinfunction "2_2") (pintype "passive"))
      (node (ref "R11") (pin "2") (pinfunction "2_2") (pintype "passive"))
    )
    (net (code "123") (name "Net-(C61-Pad1)") (class "Default")
      (node (ref "C61") (pin "1") (pinfunction "1_1") (pintype "passive"))
      (node (ref "U$3") (pin "VCAP_2") (pinfunction "VCAP_2_VCAP_2") (pintype "bidirectional"))
    )
    (net (code "124") (name "Net-(C62-Pad1)") (class "Default")
      (node (ref "C62") (pin "1") (pinfunction "1_1") (pintype "passive"))
      (node (ref "U$3") (pin "VCAP_1") (pinfunction "VCAP_1_VCAP_1") (pintype "bidirectional"))
    )
    (net (code "125") (name "Net-(C88-Pad2)") (class "Default")
      (node (ref "C88") (pin "2") (pinfunction "2_2") (pintype "passive"))
      (node (ref "R22") (pin "1") (pinfunction "1_1") (pintype "passive"))
    )
    (net (code "126") (name "Net-(J3-Pad1)") (class "Default")
      (node (ref "J3") (pin "1") (pinfunction "1_1") (pintype "passive"))
      (node (ref "T1") (pin "16") (pinfunction "16_16") (pintype "passive"))
    )
    (net (code "127") (name "Net-(J3-Pad2)") (class "Default")
      (node (ref "J3") (pin "2") (pinfunction "2_2") (pintype "passive"))
      (node (ref "T1") (pin "14") (pinfunction "14_14") (pintype "passive"))
    )
    (net (code "128") (name "Net-(J3-Pad3)") (class "Default")
      (node (ref "J3") (pin "3") (pinfunction "3_3") (pintype "passive"))
      (node (ref "T1") (pin "11") (pinfunction "11_11") (pintype "passive"))
    )
    (net (code "129") (name "Net-(J3-Pad4)") (class "Default")
      (node (ref "J3") (pin "4") (pinfunction "4_4") (pintype "passive"))
      (node (ref "J3") (pin "5") (pinfunction "5_5") (pintype "passive"))
      (node (ref "R45") (pin "2") (pinfunction "2_2") (pintype "passive"))
    )
    (net (code "130") (name "Net-(J3-Pad6)") (class "Default")
      (node (ref "J3") (pin "6") (pinfunction "6_6") (pintype "passive"))
      (node (ref "T1") (pin "9") (pinfunction "9_9") (pintype "passive"))
    )
    (net (code "131") (name "Net-(J3-Pad7)") (class "Default")
      (node (ref "J3") (pin "7") (pinfunction "7_7") (pintype "passive"))
      (node (ref "J3") (pin "8") (pinfunction "8_8") (pintype "passive"))
      (node (ref "R44") (pin "2") (pinfunction "2_2") (pintype "passive"))
    )
    (net (code "132") (name "Net-(J3-Pad9)") (class "Default")
      (node (ref "J3") (pin "9") (pinfunction "9_9") (pintype "passive"))
      (node (ref "R51") (pin "2") (pinfunction "2_2") (pintype "passive"))
    )
    (net (code "133") (name "Net-(J3-Pad11)") (class "Default")
      (node (ref "J3") (pin "11") (pinfunction "11_11") (pintype "passive"))
      (node (ref "R52") (pin "2") (pinfunction "2_2") (pintype "passive"))
    )
    (net (code "134") (name "Net-(J3-PadS1)") (class "Default")
      (node (ref "J3") (pin "S1") (pinfunction "S1_S1") (pintype "passive"))
      (node (ref "J3") (pin "S2") (pinfunction "S2_S2") (pintype "passive"))
      (node (ref "KX7RDBB102") (pin "2") (pinfunction "2_2") (pintype "passive"))
      (node (ref "R50") (pin "1") (pinfunction "1_1") (pintype "passive"))
    )
    (net (code "135") (name "Net-(JP7-Pad2)") (class "Default")
      (node (ref "JP7") (pin "2") (pinfunction "2_2") (pintype "passive"))
      (node (ref "R25") (pin "1") (pinfunction "1_1") (pintype "passive"))
    )
    (net (code "136") (name "Net-(JP7-Pad3)") (class "Default")
      (node (ref "JP7") (pin "3") (pinfunction "3_3") (pintype "passive"))
      (node (ref "R63") (pin "1") (pinfunction "1_1") (pintype "passive"))
    )
    (net (code "137") (name "Net-(JP7-Pad4)") (class "Default")
      (node (ref "JP7") (pin "4") (pinfunction "4_4") (pintype "passive"))
      (node (ref "R67") (pin "1") (pinfunction "1_1") (pintype "passive"))
    )
    (net (code "138") (name "Net-(JP7-Pad5)") (class "Default")
      (node (ref "JP7") (pin "5") (pinfunction "5_5") (pintype "passive"))
      (node (ref "R59") (pin "1") (pinfunction "1_1") (pintype "passive"))
    )
    (net (code "139") (name "Net-(JP8-Pad2)") (class "Default")
      (node (ref "JP8") (pin "2") (pinfunction "2_2") (pintype "passive"))
      (node (ref "R23") (pin "1") (pinfunction "1_1") (pintype "passive"))
    )
    (net (code "140") (name "Net-(JP8-Pad3)") (class "Default")
      (node (ref "JP8") (pin "3") (pinfunction "3_3") (pintype "passive"))
      (node (ref "R33") (pin "1") (pinfunction "1_1") (pintype "passive"))
    )
    (net (code "141") (name "Net-(JP8-Pad4)") (class "Default")
      (node (ref "JP8") (pin "4") (pinfunction "4_4") (pintype "passive"))
      (node (ref "R61") (pin "1") (pinfunction "1_1") (pintype "passive"))
    )
    (net (code "142") (name "Net-(JP9-Pad2)") (class "Default")
      (node (ref "JP9") (pin "2") (pinfunction "2_2") (pintype "passive"))
      (node (ref "R16") (pin "1") (pinfunction "1_1") (pintype "passive"))
    )
    (net (code "143") (name "Net-(JP9-Pad3)") (class "Default")
      (node (ref "JP9") (pin "3") (pinfunction "3_3") (pintype "passive"))
      (node (ref "R14") (pin "1") (pinfunction "1_1") (pintype "passive"))
    )
    (net (code "144") (name "Net-(JP9-Pad4)") (class "Default")
      (node (ref "JP9") (pin "4") (pinfunction "4_4") (pintype "passive"))
      (node (ref "R10") (pin "1") (pinfunction "1_1") (pintype "passive"))
    )
    (net (code "145") (name "Net-(JP10-Pad2)") (class "Default")
      (node (ref "JP10") (pin "2") (pinfunction "2_2") (pintype "passive"))
      (node (ref "R65") (pin "1") (pinfunction "1_1") (pintype "passive"))
    )
    (net (code "146") (name "Net-(KX7RDBB102-Pad1)") (class "Default")
      (node (ref "KX7RDBB102") (pin "1") (pinfunction "1_1") (pintype "passive"))
      (node (ref "R44") (pin "1") (pinfunction "1_1") (pintype "passive"))
      (node (ref "R45") (pin "1") (pinfunction "1_1") (pintype "passive"))
      (node (ref "R46") (pin "1") (pinfunction "1_1") (pintype "passive"))
      (node (ref "R47") (pin "1") (pinfunction "1_1") (pintype "passive"))
    )
    (net (code "147") (name "Net-(LAN8742A-CRS_DV{slash}MODE2)") (class "Default")
      (node (ref "LAN8742A") (pin "11") (pinfunction "CRS_DV/MODE2_11") (pintype "bidirectional"))
      (node (ref "R39") (pin "1") (pinfunction "1_1") (pintype "passive"))
      (node (ref "R41") (pin "1") (pinfunction "1_1") (pintype "passive"))
    )
    (net (code "148") (name "Net-(LAN8742A-RBIAS)") (class "Default")
      (node (ref "LAN8742A") (pin "24") (pinfunction "RBIAS_24") (pintype "input"))
      (node (ref "R43") (pin "2") (pinfunction "2_2") (pintype "passive"))
    )
    (net (code "149") (name "Net-(LAN8742A-RXD0{slash}MODE0)") (class "Default")
      (node (ref "LAN8742A") (pin "8") (pinfunction "RXD0/MODE0_8") (pintype "bidirectional"))
      (node (ref "R38") (pin "1") (pinfunction "1_1") (pintype "passive"))
      (node (ref "R40") (pin "1") (pinfunction "1_1") (pintype "passive"))
    )
    (net (code "150") (name "Net-(LAN8742A-RXD1{slash}MODE1)") (class "Default")
      (node (ref "LAN8742A") (pin "7") (pinfunction "RXD1/MODE1_7") (pintype "bidirectional"))
      (node (ref "R37") (pin "1") (pinfunction "1_1") (pintype "passive"))
      (node (ref "R42") (pin "1") (pinfunction "1_1") (pintype "passive"))
    )
    (net (code "151") (name "Net-(LAN8742A-RXER{slash}PHYADO)") (class "Default")
      (node (ref "LAN8742A") (pin "10") (pinfunction "RXER/PHYADO_10") (pintype "bidirectional"))
      (node (ref "R9") (pin "1") (pinfunction "1_1") (pintype "passive"))
    )
    (net (code "152") (name "Net-(LAN8742A-VDDCR)") (class "Default")
      (node (ref "C65") (pin "1") (pinfunction "1_1") (pintype "passive"))
      (node (ref "C66") (pin "1") (pinfunction "1_1") (pintype "passive"))
      (node (ref "LAN8742A") (pin "6") (pinfunction "VDDCR_6") (pintype "power_in"))
    )
    (net (code "153") (name "Net-(LAN8742A-~{NINT}{slash}REFCLKO)") (class "Default")
      (node (ref "LAN8742A") (pin "14") (pinfunction "~{NINT}/REFCLKO_14") (pintype "output"))
      (node (ref "R48") (pin "1") (pinfunction "1_1") (pintype "passive"))
    )
    (net (code "154") (name "Net-(LAN8742A-~{NRST})") (class "Default")
      (node (ref "LAN8742A") (pin "15") (pinfunction "~{NRST}_15") (pintype "input"))
      (node (ref "R49") (pin "2") (pinfunction "2_2") (pintype "passive"))
    )
    (net (code "155") (name "Net-(LED1-PadC)") (class "Default")
      (node (ref "LED1") (pin "C") (pinfunction "C_C") (pintype "passive"))
      (node (ref "R2") (pin "2") (pinfunction "2_2") (pintype "passive"))
    )
    (net (code "156") (name "Net-(LED2-PadA)") (class "Default")
      (node (ref "LED2") (pin "A") (pinfunction "A_A") (pintype "passive"))
      (node (ref "U$3") (pin "PG14") (pinfunction "PG14_PG14") (pintype "bidirectional"))
    )
    (net (code "157") (name "Net-(LED2-PadC)") (class "Default")
      (node (ref "LED2") (pin "C") (pinfunction "C_C") (pintype "passive"))
      (node (ref "R34") (pin "2") (pinfunction "2_2") (pintype "passive"))
    )
    (net (code "158") (name "Net-(LED3-PadC)") (class "Default")
      (node (ref "LED3") (pin "C") (pinfunction "C_C") (pintype "passive"))
      (node (ref "R3") (pin "2") (pinfunction "2_2") (pintype "passive"))
    )
    (net (code "159") (name "Net-(LED4-PadA)") (class "Default")
      (node (ref "LED4") (pin "A") (pinfunction "A_A") (pintype "passive"))
      (node (ref "U$3") (pin "PA15") (pinfunction "PA15_PA15") (pintype "bidirectional"))
    )
    (net (code "160") (name "Net-(LED4-PadC)") (class "Default")
      (node (ref "LED4") (pin "C") (pinfunction "C_C") (pintype "passive"))
      (node (ref "R69") (pin "2") (pinfunction "2_2") (pintype "passive"))
    )
    (net (code "161") (name "Net-(LED5-PadA)") (class "Default")
      (node (ref "LED5") (pin "A") (pinfunction "A_A") (pintype "passive"))
      (node (ref "U$3") (pin "PH9") (pinfunction "PH9_PH9") (pintype "bidirectional"))
    )
    (net (code "162") (name "Net-(LED5-PadC)") (class "Default")
      (node (ref "LED5") (pin "C") (pinfunction "C_C") (pintype "passive"))
      (node (ref "R70") (pin "2") (pinfunction "2_2") (pintype "passive"))
    )
    (net (code "163") (name "Net-(LED6-PadA)") (class "Default")
      (node (ref "LED6") (pin "A") (pinfunction "A_A") (pintype "passive"))
      (node (ref "U$3") (pin "PA6") (pinfunction "PA6_PA6") (pintype "bidirectional"))
    )
    (net (code "164") (name "Net-(LED6-PadC)") (class "Default")
      (node (ref "LED6") (pin "C") (pinfunction "C_C") (pintype "passive"))
      (node (ref "R71") (pin "2") (pinfunction "2_2") (pintype "passive"))
    )
    (net (code "165") (name "Net-(Q1-D-Pad2)") (class "Default")
      (node (ref "Q1") (pin "2") (pinfunction "D_2") (pintype "passive"))
      (node (ref "Q1") (pin "4") (pinfunction "D_4") (pintype "passive"))
      (node (ref "R5") (pin "1") (pinfunction "1_1") (pintype "passive"))
      (node (ref "R7") (pin "2") (pinfunction "2_2") (pintype "passive"))
    )
    (net (code "166") (name "Net-(Q1-S)") (class "Default")
      (node (ref "Q1") (pin "3") (pinfunction "S_3") (pintype "passive"))
      (node (ref "Q2") (pin "B") (pinfunction "B_B") (pintype "passive"))
      (node (ref "R4") (pin "2") (pinfunction "2_2") (pintype "passive"))
    )
    (net (code "167") (name "Net-(R12-Pad2)") (class "Default")
      (node (ref "R12") (pin "2") (pinfunction "2_2") (pintype "passive"))
      (node (ref "X4") (pin "2") (pinfunction "2_2") (pintype "passive"))
    )
    (net (code "168") (name "Net-(R26-Pad2)") (class "Default")
      (node (ref "R26") (pin "2") (pinfunction "2_2") (pintype "passive"))
      (node (ref "U$3") (pin "PH12") (pinfunction "PH12_PH12") (pintype "bidirectional"))
    )
    (net (code "169") (name "Net-(R36-Pad2)") (class "Default")
      (node (ref "R36") (pin "2") (pinfunction "2_2") (pintype "passive"))
      (node (ref "X4") (pin "3") (pinfunction "3_3") (pintype "passive"))
    )
    (net (code "170") (name "Net-(R46-Pad2)") (class "Default")
      (node (ref "R46") (pin "2") (pinfunction "2_2") (pintype "passive"))
      (node (ref "T1") (pin "15") (pinfunction "15_15") (pintype "passive"))
    )
    (net (code "171") (name "Net-(R47-Pad2)") (class "Default")
      (node (ref "R47") (pin "2") (pinfunction "2_2") (pintype "passive"))
      (node (ref "T1") (pin "10") (pinfunction "10_10") (pintype "passive"))
    )
    (net (code "172") (name "Net-(SJ2-Pad2)") (class "Default")
      (node (ref "SJ2") (pin "2") (pinfunction "2_2") (pintype "passive"))
      (node (ref "U$3") (pin "PB2/BOOT1") (pinfunction "PB2/BOOT1_PB2/BOOT1") (pintype "bidirectional"))
    )
    (net (code "173") (name "Net-(SJ3-Pad2)") (class "Default")
      (node (ref "SJ3") (pin "2") (pinfunction "2_2") (pintype "passive"))
      (node (ref "U$3") (pin "BOOT0") (pinfunction "BOOT0_BOOT0") (pintype "bidirectional"))
    )
    (net (code "174") (name "Net-(U$2-BYP)") (class "Default")
      (node (ref "C17") (pin "2") (pinfunction "2_2") (pintype "passive"))
      (node (ref "U$2") (pin "4") (pinfunction "BYP_4") (pintype "bidirectional"))
    )
    (net (code "175") (name "Net-(U$2-OUT)") (class "Default")
      (node (ref "C17") (pin "1") (pinfunction "1_1") (pintype "passive"))
      (node (ref "C18") (pin "1") (pinfunction "1_1") (pintype "passive"))
      (node (ref "SJ1") (pin "3") (pinfunction "3_3") (pintype "passive"))
      (node (ref "U$2") (pin "1") (pinfunction "OUT_1") (pintype "bidirectional"))
      (node (ref "U$2") (pin "2") (pinfunction "SENS_2") (pintype "bidirectional"))
    )
    (net (code "176") (name "Net-(U$6-P$3)") (class "Default")
      (node (ref "R10") (pin "2") (pinfunction "2_2") (pintype "passive"))
      (node (ref "R13") (pin "1") (pinfunction "1_1") (pintype "passive"))
      (node (ref "U$6") (pin "3") (pinfunction "P$3_3") (pintype "bidirectional"))
    )
    (net (code "177") (name "Net-(U$8-P$3)") (class "Default")
      (node (ref "R14") (pin "2") (pinfunction "2_2") (pintype "passive"))
      (node (ref "R15") (pin "1") (pinfunction "1_1") (pintype "passive"))
      (node (ref "U$8") (pin "3") (pinfunction "P$3_3") (pintype "bidirectional"))
    )
    (net (code "178") (name "Net-(U$9-P$3)") (class "Default")
      (node (ref "R16") (pin "2") (pinfunction "2_2") (pintype "passive"))
      (node (ref "R17") (pin "1") (pinfunction "1_1") (pintype "passive"))
      (node (ref "U$9") (pin "3") (pinfunction "P$3_3") (pintype "bidirectional"))
    )
    (net (code "179") (name "Net-(U$10-P$3)") (class "Default")
      (node (ref "R23") (pin "2") (pinfunction "2_2") (pintype "passive"))
      (node (ref "R24") (pin "1") (pinfunction "1_1") (pintype "passive"))
      (node (ref "U$10") (pin "3") (pinfunction "P$3_3") (pintype "bidirectional"))
    )
    (net (code "180") (name "Net-(U$11-P$3)") (class "Default")
      (node (ref "R25") (pin "2") (pinfunction "2_2") (pintype "passive"))
      (node (ref "R32") (pin "1") (pinfunction "1_1") (pintype "passive"))
      (node (ref "U$11") (pin "3") (pinfunction "P$3_3") (pintype "bidirectional"))
    )
    (net (code "181") (name "Net-(U$12-P$3)") (class "Default")
      (node (ref "R33") (pin "2") (pinfunction "2_2") (pintype "passive"))
      (node (ref "R35") (pin "1") (pinfunction "1_1") (pintype "passive"))
      (node (ref "U$12") (pin "3") (pinfunction "P$3_3") (pintype "bidirectional"))
    )
    (net (code "182") (name "Net-(U$13-P$3)") (class "Default")
      (node (ref "R59") (pin "2") (pinfunction "2_2") (pintype "passive"))
      (node (ref "R60") (pin "1") (pinfunction "1_1") (pintype "passive"))
      (node (ref "U$13") (pin "3") (pinfunction "P$3_3") (pintype "bidirectional"))
    )
    (net (code "183") (name "Net-(U$14-P$3)") (class "Default")
      (node (ref "R61") (pin "2") (pinfunction "2_2") (pintype "passive"))
      (node (ref "R62") (pin "1") (pinfunction "1_1") (pintype "passive"))
      (node (ref "U$14") (pin "3") (pinfunction "P$3_3") (pintype "bidirectional"))
    )
    (net (code "184") (name "Net-(U$15-P$3)") (class "Default")
      (node (ref "R63") (pin "2") (pinfunction "2_2") (pintype "passive"))
      (node (ref "R64") (pin "1") (pinfunction "1_1") (pintype "passive"))
      (node (ref "U$15") (pin "3") (pinfunction "P$3_3") (pintype "bidirectional"))
    )
    (net (code "185") (name "Net-(U$16-P$3)") (class "Default")
      (node (ref "R65") (pin "2") (pinfunction "2_2") (pintype "passive"))
      (node (ref "R66") (pin "1") (pinfunction "1_1") (pintype "passive"))
      (node (ref "U$16") (pin "3") (pinfunction "P$3_3") (pintype "bidirectional"))
    )
    (net (code "186") (name "Net-(U$17-P$3)") (class "Default")
      (node (ref "R67") (pin "2") (pinfunction "2_2") (pintype "passive"))
      (node (ref "R68") (pin "1") (pinfunction "1_1") (pintype "passive"))
      (node (ref "U$17") (pin "3") (pinfunction "P$3_3") (pintype "bidirectional"))
    )
    (net (code "187") (name "Net-(U1-INTERRUPT)") (class "Default")
      (node (ref "R31") (pin "2") (pinfunction "2_2") (pintype "passive"))
      (node (ref "U1") (pin "37") (pinfunction "INTERRUPT_37") (pintype "output"))
    )
    (net (code "188") (name "Net-(U1-LDO)") (class "Default")
      (node (ref "C5") (pin "1") (pinfunction "1_1") (pintype "passive"))
      (node (ref "U1") (pin "43") (pinfunction "LDO_43") (pintype "output"))
    )
    (net (code "189") (name "Net-(U1-Q1)") (class "Default")
      (node (ref "C3") (pin "1") (pinfunction "1_1") (pintype "passive"))
      (node (ref "U1") (pin "48") (pinfunction "Q1_48") (pintype "passive"))
    )
    (net (code "190") (name "Net-(U1-Q2)") (class "Default")
      (node (ref "C3") (pin "2") (pinfunction "2_2") (pintype "passive"))
      (node (ref "U1") (pin "47") (pinfunction "Q2_47") (pintype "passive"))
    )
    (net (code "191") (name "Net-(U1-Q3)") (class "Default")
      (node (ref "C4") (pin "1") (pinfunction "1_1") (pintype "passive"))
      (node (ref "U1") (pin "46") (pinfunction "Q3_46") (pintype "passive"))
    )
    (net (code "192") (name "Net-(U1-SCK)") (class "Default")
      (node (ref "R28") (pin "1") (pinfunction "1_1") (pintype "passive"))
      (node (ref "U1") (pin "38") (pinfunction "SCK_38") (pintype "input"))
    )
    (net (code "193") (name "Net-(U1-SDI)") (class "Default")
      (node (ref "R") (pin "1") (pinfunction "1_1") (pintype "passive"))
      (node (ref "U1") (pin "40") (pinfunction "SDI_40") (pintype "input"))
    )
    (net (code "194") (name "Net-(U1-SDO)") (class "Default")
      (node (ref "R27") (pin "1") (pinfunction "1_1") (pintype "passive"))
      (node (ref "U1") (pin "39") (pinfunction "SDO_39") (pintype "output"))
    )
    (net (code "195") (name "Net-(U1-VREFOUT)") (class "Default")
      (node (ref "C1") (pin "1") (pinfunction "1_1") (pintype "passive"))
      (node (ref "U1") (pin "13") (pinfunction "VREFOUT_13") (pintype "power_in"))
      (node (ref "U1") (pin "14") (pinfunction "VREFP_14") (pintype "power_in"))
    )
    (net (code "196") (name "Net-(U1-VREF_BYP)") (class "Default")
      (node (ref "C2") (pin "1") (pinfunction "1_1") (pintype "passive"))
      (node (ref "U1") (pin "11") (pinfunction "VREF_BYP_11") (pintype "passive"))
    )
    (net (code "197") (name "Net-(U1-~{CS})") (class "Default")
      (node (ref "R29") (pin "1") (pinfunction "1_1") (pintype "passive"))
      (node (ref "U1") (pin "41") (pinfunction "~{CS}_41") (pintype "input"))
    )
    (net (code "198") (name "Net-(U1-~{RESET})") (class "Default")
      (node (ref "R30") (pin "1") (pinfunction "1_1") (pintype "passive"))
      (node (ref "U1") (pin "42") (pinfunction "~{RESET}_42") (pintype "input"))
    )
    (net (code "199") (name "Net-(U2-SET)") (class "Default")
      (node (ref "RSET") (pin "2") (pinfunction "2_2") (pintype "passive"))
      (node (ref "U2") (pin "7") (pinfunction "SET_7") (pintype "input"))
    )
    (net (code "200") (name "Net-(U2-VIN)") (class "Default")
      (node (ref "C6") (pin "1") (pinfunction "1_1") (pintype "passive"))
      (node (ref "R6") (pin "2") (pinfunction "2_2") (pintype "passive"))
      (node (ref "R8") (pin "2") (pinfunction "2_2") (pintype "passive"))
      (node (ref "U2") (pin "6") (pinfunction "VIN_6") (pintype "input"))
    )
    (net (code "201") (name "Net-(U2-VSP)") (class "Default")
      (node (ref "C12") (pin "1") (pinfunction "1_1") (pintype "passive"))
      (node (ref "C13") (pin "1") (pinfunction "1_1") (pintype "passive"))
      (node (ref "RDAMP") (pin "2") (pinfunction "2_2") (pintype "passive"))
      (node (ref "U2") (pin "1") (pinfunction "VSP_1") (pintype "power_in"))
    )
    (net (code "202") (name "Net-(U6-BOOT)") (class "Default")
      (node (ref "C90") (pin "1") (pinfunction "1_1") (pintype "passive"))
      (node (ref "U6") (pin "1") (pinfunction "BOOT_1") (pintype "output"))
    )
    (net (code "203") (name "Net-(U6-COMP)") (class "Default")
      (node (ref "C88") (pin "1") (pinfunction "1_1") (pintype "passive"))
      (node (ref "C89") (pin "1") (pinfunction "1_1") (pintype "passive"))
      (node (ref "U6") (pin "6") (pinfunction "COMP_6") (pintype "output"))
    )
    (net (code "204") (name "Net-(U6-PH)") (class "Default")
      (node (ref "C90") (pin "2") (pinfunction "2_2") (pintype "passive"))
      (node (ref "D1") (pin "C") (pinfunction "C_C") (pintype "passive"))
      (node (ref "L1") (pin "1") (pinfunction "1_1") (pintype "passive"))
      (node (ref "U6") (pin "8") (pinfunction "PH_8") (pintype "output"))
    )
    (net (code "205") (name "Net-(U6-SS)") (class "Default")
      (node (ref "C84") (pin "1") (pinfunction "1_1") (pintype "passive"))
      (node (ref "U6") (pin "4") (pinfunction "SS_4") (pintype "input"))
    )
    (net (code "206") (name "Net-(U6-VSENSE)") (class "Default")
      (node (ref "R20") (pin "1") (pinfunction "1_1") (pintype "passive"))
      (node (ref "R21") (pin "2") (pinfunction "2_2") (pintype "passive"))
      (node (ref "U6") (pin "5") (pinfunction "VSENSE_5") (pintype "input"))
    )
    (net (code "207") (name "OUT") (class "Default")
      (node (ref "R66") (pin "2") (pinfunction "2_2") (pintype "passive"))
      (node (ref "U$3") (pin "PF6") (pinfunction "PF6_PF6") (pintype "bidirectional"))
    )
    (net (code "208") (name "OUT1") (class "Default")
      (node (ref "R64") (pin "2") (pinfunction "2_2") (pintype "passive"))
      (node (ref "U$3") (pin "PG9") (pinfunction "PG9_PG9") (pintype "bidirectional"))
    )
    (net (code "209") (name "OUT2") (class "Default")
      (node (ref "R32") (pin "2") (pinfunction "2_2") (pintype "passive"))
      (node (ref "U$3") (pin "PG10") (pinfunction "PG10_PG10") (pintype "bidirectional"))
    )
    (net (code "210") (name "OUT3") (class "Default")
      (node (ref "R60") (pin "2") (pinfunction "2_2") (pintype "passive"))
      (node (ref "U$3") (pin "PF7") (pinfunction "PF7_PF7") (pintype "bidirectional"))
    )
    (net (code "211") (name "OUT4") (class "Default")
      (node (ref "R68") (pin "2") (pinfunction "2_2") (pintype "passive"))
      (node (ref "U$3") (pin "PI11") (pinfunction "PI11_PI11") (pintype "bidirectional"))
    )
    (net (code "212") (name "RSENS+") (class "Default")
      (node (ref "RT0805BRD072K05L") (pin "1") (pinfunction "1_1") (pintype "passive"))
      (node (ref "U1") (pin "16") (pinfunction "CH1_16") (pintype "input"))
    )
    (net (code "213") (name "RSENS-") (class "Default")
      (node (ref "JP1") (pin "2") (pinfunction "2_2") (pintype "passive"))
      (node (ref "JP1") (pin "4") (pinfunction "4_4") (pintype "passive"))
      (node (ref "JP1") (pin "6") (pinfunction "6_6") (pintype "passive"))
      (node (ref "JP2") (pin "2") (pinfunction "2_2") (pintype "passive"))
      (node (ref "JP2") (pin "4") (pinfunction "4_4") (pintype "passive"))
      (node (ref "JP2") (pin "6") (pinfunction "6_6") (pintype "passive"))
      (node (ref "JP3") (pin "2") (pinfunction "2_2") (pintype "passive"))
      (node (ref "JP3") (pin "4") (pinfunction "4_4") (pintype "passive"))
      (node (ref "JP3") (pin "6") (pinfunction "6_6") (pintype "passive"))
      (node (ref "RT0805BRD072K05L") (pin "2") (pinfunction "2_2") (pintype "passive"))
      (node (ref "U1") (pin "17") (pinfunction "CH2_17") (pintype "input"))
      (node (ref "U1") (pin "18") (pinfunction "CH3_18") (pintype "input"))
      (node (ref "U1") (pin "20") (pinfunction "CH5_20") (pintype "input"))
      (node (ref "U1") (pin "22") (pinfunction "CH7_22") (pintype "input"))
      (node (ref "U1") (pin "24") (pinfunction "CH9_24") (pintype "input"))
      (node (ref "U1") (pin "26") (pinfunction "CH11_26") (pintype "input"))
      (node (ref "U1") (pin "28") (pinfunction "CH13_28") (pintype "input"))
      (node (ref "U1") (pin "30") (pinfunction "CH15_30") (pintype "input"))
      (node (ref "U1") (pin "32") (pinfunction "CH17_32") (pintype "input"))
      (node (ref "U1") (pin "34") (pinfunction "CH19_34") (pintype "input"))
    )
    (net (code "214") (name "RXN") (class "Default")
      (node (ref "LAN8742A") (pin "22") (pinfunction "RXN_22") (pintype "bidirectional"))
      (node (ref "R58") (pin "2") (pinfunction "2_2") (pintype "passive"))
      (node (ref "T1") (pin "8") (pinfunction "8_8") (pintype "passive"))
      (node (ref "U4") (pin "6") (pinfunction "IO4_6") (pintype "bidirectional"))
    )
    (net (code "215") (name "RXP") (class "Default")
      (node (ref "LAN8742A") (pin "23") (pinfunction "RXP_23") (pintype "bidirectional"))
      (node (ref "R57") (pin "2") (pinfunction "2_2") (pintype "passive"))
      (node (ref "T1") (pin "6") (pinfunction "6_6") (pintype "passive"))
      (node (ref "U4") (pin "1") (pinfunction "IO1_1") (pintype "bidirectional"))
    )
    (net (code "216") (name "STLINK_RX") (class "Default")
      (node (ref "U$3") (pin "PA10") (pinfunction "PA10_PA10") (pintype "bidirectional"))
      (node (ref "U$5") (pin "8") (pinfunction "8_8") (pintype "passive"))
    )
    (net (code "217") (name "STLINK_TX") (class "Default")
      (node (ref "U$3") (pin "PB6") (pinfunction "PB6_PB6") (pintype "bidirectional"))
      (node (ref "U$5") (pin "7") (pinfunction "7_7") (pintype "passive"))
    )
    (net (code "218") (name "SWCLK") (class "Default")
      (node (ref "U$3") (pin "PA14") (pinfunction "PA14_PA14") (pintype "bidirectional"))
      (node (ref "U$5") (pin "3") (pinfunction "3_3") (pintype "passive"))
    )
    (net (code "219") (name "SWDIO") (class "Default")
      (node (ref "U$3") (pin "PA13") (pinfunction "PA13_PA13") (pintype "bidirectional"))
      (node (ref "U$5") (pin "4") (pinfunction "4_4") (pintype "passive"))
    )
    (net (code "220") (name "SWO") (class "Default")
      (node (ref "U$5") (pin "2") (pinfunction "2_2") (pintype "passive"))
    )
    (net (code "221") (name "TXN") (class "Default")
      (node (ref "LAN8742A") (pin "20") (pinfunction "TXN_20") (pintype "bidirectional"))
      (node (ref "R56") (pin "2") (pinfunction "2_2") (pintype "passive"))
      (node (ref "T1") (pin "3") (pinfunction "3_3") (pintype "passive"))
      (node (ref "U4") (pin "4") (pinfunction "IO3_4") (pintype "bidirectional"))
    )
    (net (code "222") (name "TXP") (class "Default")
      (node (ref "LAN8742A") (pin "21") (pinfunction "TXP_21") (pintype "bidirectional"))
      (node (ref "R55") (pin "2") (pinfunction "2_2") (pintype "passive"))
      (node (ref "T1") (pin "1") (pinfunction "1_1") (pintype "passive"))
      (node (ref "U4") (pin "3") (pinfunction "IO2_3") (pintype "bidirectional"))
    )
    (net (code "223") (name "USB_OTG_FS_DM") (class "Default")
      (node (ref "ESDA6V1BC6") (pin "6") (pinfunction "6_6") (pintype "passive"))
      (node (ref "R12") (pin "1") (pinfunction "1_1") (pintype "passive"))
      (node (ref "U$3") (pin "PA11") (pinfunction "PA11_PA11") (pintype "bidirectional"))
    )
    (net (code "224") (name "USB_OTG_FS_DP") (class "Default")
      (node (ref "ESDA6V1BC6") (pin "4") (pinfunction "4_4") (pintype "passive"))
      (node (ref "R36") (pin "1") (pinfunction "1_1") (pintype "passive"))
      (node (ref "U$3") (pin "PA12") (pinfunction "PA12_PA12") (pintype "bidirectional"))
    )
    (net (code "225") (name "USB_OTG_FS_VBUS") (class "Default")
      (node (ref "ESDA6V1BC6") (pin "1") (pinfunction "1_1") (pintype "passive"))
      (node (ref "U$3") (pin "PA9") (pinfunction "PA9_PA9") (pintype "bidirectional"))
      (node (ref "X4") (pin "1") (pinfunction "1_1") (pintype "passive"))
    )
    (net (code "226") (name "VCC") (class "Default")
      (node (ref "C35") (pin "1") (pinfunction "1_1") (pintype "passive"))
      (node (ref "C36") (pin "1") (pinfunction "1_1") (pintype "passive"))
      (node (ref "C49") (pin "2") (pinfunction "2_2") (pintype "passive"))
      (node (ref "C56") (pin "2") (pinfunction "2_2") (pintype "passive"))
      (node (ref "SJ1") (pin "2") (pinfunction "2_2") (pintype "passive"))
      (node (ref "U$3") (pin "VDDA") (pinfunction "VDDA_VDDA") (pintype "bidirectional"))
      (node (ref "U1") (pin "2") (pinfunction "VDD_2") (pintype "power_in"))
      (node (ref "U1") (pin "4") (pinfunction "VDD_4") (pintype "power_in"))
      (node (ref "U1") (pin "45") (pinfunction "VDD_45") (pintype "power_in"))
      (node (ref "U1") (pin "6") (pinfunction "VDD_6") (pintype "power_in"))
      (node (ref "U1") (pin "8") (pinfunction "VDD_8") (pintype "power_in"))
    )
    (net (code "227") (name "VDD_ETH") (class "Default")
      (node (ref "C21") (pin "1") (pinfunction "1_1") (pintype "passive"))
      (node (ref "C48") (pin "1") (pinfunction "1_1") (pintype "passive"))
      (node (ref "C63") (pin "+") (pinfunction "+_+") (pintype "passive"))
      (node (ref "C64") (pin "1") (pinfunction "1_1") (pintype "passive"))
      (node (ref "C68") (pin "1") (pinfunction "1_1") (pintype "passive"))
      (node (ref "C71") (pin "1") (pinfunction "1_1") (pintype "passive"))
      (node (ref "LAN8742A") (pin "1") (pinfunction "VDD2A_1") (pintype "power_in"))
      (node (ref "LAN8742A") (pin "19") (pinfunction "VDD1A_19") (pintype "power_in"))
      (node (ref "LBEAD") (pin "1") (pinfunction "1_1") (pintype "passive"))
      (node (ref "R55") (pin "1") (pinfunction "1_1") (pintype "passive"))
      (node (ref "R56") (pin "1") (pinfunction "1_1") (pintype "passive"))
      (node (ref "R57") (pin "1") (pinfunction "1_1") (pintype "passive"))
      (node (ref "R58") (pin "1") (pinfunction "1_1") (pintype "passive"))
      (node (ref "T1") (pin "2") (pinfunction "2_2") (pintype "passive"))
      (node (ref "T1") (pin "7") (pinfunction "7_7") (pintype "passive"))
      (node (ref "U4") (pin "5") (pinfunction "VBUS_5") (pintype "power_in"))
    )
    (net (code "228") (name "VG") (class "Default")
      (node (ref "Q1") (pin "1") (pinfunction "G_1") (pintype "passive"))
      (node (ref "Q2") (pin "C") (pinfunction "C_C") (pintype "passive"))
      (node (ref "U2") (pin "3") (pinfunction "VG_3") (pintype "output"))
    )
    (net (code "229") (name "VREF3.0") (class "Default")
      (node (ref "C34") (pin "1") (pinfunction "1_1") (pintype "passive"))
      (node (ref "C37") (pin "1") (pinfunction "1_1") (pintype "passive"))
      (node (ref "C8") (pin "1") (pinfunction "1_1") (pintype "passive"))
      (node (ref "R8") (pin "1") (pinfunction "1_1") (pintype "passive"))
      (node (ref "U$3") (pin "VREF") (pinfunction "VREF_VREF") (pintype "bidirectional"))
      (node (ref "U2") (pin "4") (pinfunction "REGS_4") (pintype "input"))
      (node (ref "U2") (pin "5") (pinfunction "REGF_5") (pintype "input"))
    )
    (net (code "230") (name "X1") (class "Default")
      (node (ref "C70") (pin "1") (pinfunction "1_1") (pintype "passive"))
      (node (ref "LAN8742A") (pin "5") (pinfunction "XTAL1/CLKLN_5") (pintype "input"))
      (node (ref "Y1") (pin "1") (pinfunction "IN/OUT_1") (pintype "bidirectional"))
    )
    (net (code "231") (name "X2") (class "Default")
      (node (ref "C69") (pin "1") (pinfunction "1_1") (pintype "passive"))
      (node (ref "LAN8742A") (pin "4") (pinfunction "XTAL2_4") (pintype "output"))
      (node (ref "Y1") (pin "3") (pinfunction "OUT/IN_3") (pintype "bidirectional"))
    )
    (net (code "232") (name "XTR_DAC") (class "Default")
      (node (ref "C57") (pin "1") (pinfunction "1_1") (pintype "passive"))
      (node (ref "R6") (pin "1") (pinfunction "1_1") (pintype "passive"))
      (node (ref "U$3") (pin "PA4") (pinfunction "PA4_PA4") (pintype "bidirectional"))
    )
    (net (code "233") (name "XTR_EF") (class "Default")
      (node (ref "U$3") (pin "PF9") (pinfunction "PF9_PF9") (pintype "bidirectional"))
      (node (ref "U2") (pin "8") (pinfunction "~{EF}_8") (pintype "input"))
    )
    (net (code "234") (name "XTR_EN") (class "Default")
      (node (ref "U$3") (pin "PF8") (pinfunction "PF8_PF8") (pintype "bidirectional"))
      (node (ref "U2") (pin "9") (pinfunction "OD_9") (pintype "output"))
    )
    (net (code "235") (name "unconnected-(ESDA6V1BC6-Pad3)") (class "Default")
      (node (ref "ESDA6V1BC6") (pin "3") (pinfunction "3_3") (pintype "passive"))
    )
    (net (code "236") (name "unconnected-(S1-Pad5)") (class "Default")
      (node (ref "S1") (pin "5") (pinfunction "5_5") (pintype "passive"))
    )
    (net (code "237") (name "unconnected-(U$3-PadPA8)") (class "Default")
      (node (ref "U$3") (pin "PA8") (pinfunction "PA8_PA8") (pintype "bidirectional"))
    )
    (net (code "238") (name "unconnected-(U$3-PadPB4)") (class "Default")
      (node (ref "U$3") (pin "PB4") (pinfunction "PB4_PB4") (pintype "bidirectional"))
    )
    (net (code "239") (name "unconnected-(U$3-PadPB7)") (class "Default")
      (node (ref "U$3") (pin "PB7") (pinfunction "PB7_PB7") (pintype "bidirectional"))
    )
    (net (code "240") (name "unconnected-(U$3-PadPB14)") (class "Default")
      (node (ref "U$3") (pin "PB14") (pinfunction "PB14_PB14") (pintype "bidirectional"))
    )
    (net (code "241") (name "unconnected-(U$3-PadPB15)") (class "Default")
      (node (ref "U$3") (pin "PB15") (pinfunction "PB15_PB15") (pintype "bidirectional"))
    )
    (net (code "242") (name "unconnected-(U$3-PadPC8)") (class "Default")
      (node (ref "U$3") (pin "PC8") (pinfunction "PC8_PC8") (pintype "bidirectional"))
    )
    (net (code "243") (name "unconnected-(U$3-PadPC9)") (class "Default")
      (node (ref "U$3") (pin "PC9") (pinfunction "PC9_PC9") (pintype "bidirectional"))
    )
    (net (code "244") (name "unconnected-(U$3-PadPC10)") (class "Default")
      (node (ref "U$3") (pin "PC10") (pinfunction "PC10_PC10") (pintype "bidirectional"))
    )
    (net (code "245") (name "unconnected-(U$3-PadPC11)") (class "Default")
      (node (ref "U$3") (pin "PC11") (pinfunction "PC11_PC11") (pintype "bidirectional"))
    )
    (net (code "246") (name "unconnected-(U$3-PadPC12)") (class "Default")
      (node (ref "U$3") (pin "PC12") (pinfunction "PC12_PC12") (pintype "bidirectional"))
    )
    (net (code "247") (name "unconnected-(U$3-PadPC13)") (class "Default")
      (node (ref "U$3") (pin "PC13") (pinfunction "PC13_PC13") (pintype "bidirectional"))
    )
    (net (code "248") (name "unconnected-(U$3-PadPC14)") (class "Default")
      (node (ref "U$3") (pin "PC14") (pinfunction "PC14_PC14") (pintype "bidirectional"))
    )
    (net (code "249") (name "unconnected-(U$3-PadPC15)") (class "Default")
      (node (ref "U$3") (pin "PC15") (pinfunction "PC15_PC15") (pintype "bidirectional"))
    )
    (net (code "250") (name "unconnected-(U$3-PadPD2)") (class "Default")
      (node (ref "U$3") (pin "PD2") (pinfunction "PD2_PD2") (pintype "bidirectional"))
    )
    (net (code "251") (name "unconnected-(U$3-PadPD4)") (class "Default")
      (node (ref "U$3") (pin "PD4") (pinfunction "PD4_PD4") (pintype "bidirectional"))
    )
    (net (code "252") (name "unconnected-(U$3-PadPD5)") (class "Default")
      (node (ref "U$3") (pin "PD5") (pinfunction "PD5_PD5") (pintype "bidirectional"))
    )
    (net (code "253") (name "unconnected-(U$3-PadPD7)") (class "Default")
      (node (ref "U$3") (pin "PD7") (pinfunction "PD7_PD7") (pintype "bidirectional"))
    )
    (net (code "254") (name "unconnected-(U$3-PadPD11)") (class "Default")
      (node (ref "U$3") (pin "PD11") (pinfunction "PD11_PD11") (pintype "bidirectional"))
    )
    (net (code "255") (name "unconnected-(U$3-PadPDR_ON)") (class "Default")
      (node (ref "U$3") (pin "PDR_ON") (pinfunction "PDR_ON_PDR_ON") (pintype "bidirectional"))
    )
    (net (code "256") (name "unconnected-(U$3-PadPG2)") (class "Default")
      (node (ref "U$3") (pin "PG2") (pinfunction "PG2_PG2") (pintype "bidirectional"))
    )
    (net (code "257") (name "unconnected-(U$3-PadPG3)") (class "Default")
      (node (ref "U$3") (pin "PG3") (pinfunction "PG3_PG3") (pintype "bidirectional"))
    )
    (net (code "258") (name "unconnected-(U$3-PadPG13)") (class "Default")
      (node (ref "U$3") (pin "PG13") (pinfunction "PG13_PG13") (pintype "bidirectional"))
    )
    (net (code "259") (name "unconnected-(U$3-PadPH0)") (class "Default")
      (node (ref "U$3") (pin "PH0") (pinfunction "PH0_PH0") (pintype "bidirectional"))
    )
    (net (code "260") (name "unconnected-(U$3-PadPH1)") (class "Default")
      (node (ref "U$3") (pin "PH1") (pinfunction "PH1_PH1") (pintype "bidirectional"))
    )
    (net (code "261") (name "unconnected-(U$3-PadPH15)") (class "Default")
      (node (ref "U$3") (pin "PH15") (pinfunction "PH15_PH15") (pintype "bidirectional"))
    )
    (net (code "262") (name "unconnected-(U$3-PadPI3)") (class "Default")
      (node (ref "U$3") (pin "PI3") (pinfunction "PI3_PI3") (pintype "bidirectional"))
    )
    (net (code "263") (name "unconnected-(U$3-PadPI8)") (class "Default")
      (node (ref "U$3") (pin "PI8") (pinfunction "PI8_PI8") (pintype "bidirectional"))
    )
    (net (code "264") (name "unconnected-(U$4-IO3{slash}~{RESET}-Pad1)") (class "Default")
      (node (ref "U$4") (pin "1") (pinfunction "IO3/~{RESET}_1") (pintype "bidirectional"))
    )
    (net (code "265") (name "unconnected-(U$4-~{RESET}-Pad3)") (class "Default")
      (node (ref "U$4") (pin "3") (pinfunction "~{RESET}_3") (pintype "bidirectional"))
    )
    (net (code "266") (name "unconnected-(U$4-~{WP}-Pad9)") (class "Default")
      (node (ref "U$4") (pin "9") (pinfunction "~{WP}_9") (pintype "bidirectional"))
    )
    (net (code "267") (name "unconnected-(X4-Pad4)") (class "Default")
      (node (ref "X4") (pin "4") (pinfunction "4_4") (pintype "passive"))
    )
    (net (code "268") (name "~{EN}") (class "Default")
      (node (ref "R18") (pin "1") (pinfunction "1_1") (pintype "passive"))
      (node (ref "R19") (pin "2") (pinfunction "2_2") (pintype "passive"))
      (node (ref "U6") (pin "3") (pinfunction "EN_3") (pintype "input"))
    )
  )
)
